# slimarm_apricot_nand.net
KiCad netlist of a schematic drawn in EasyEDA Pro
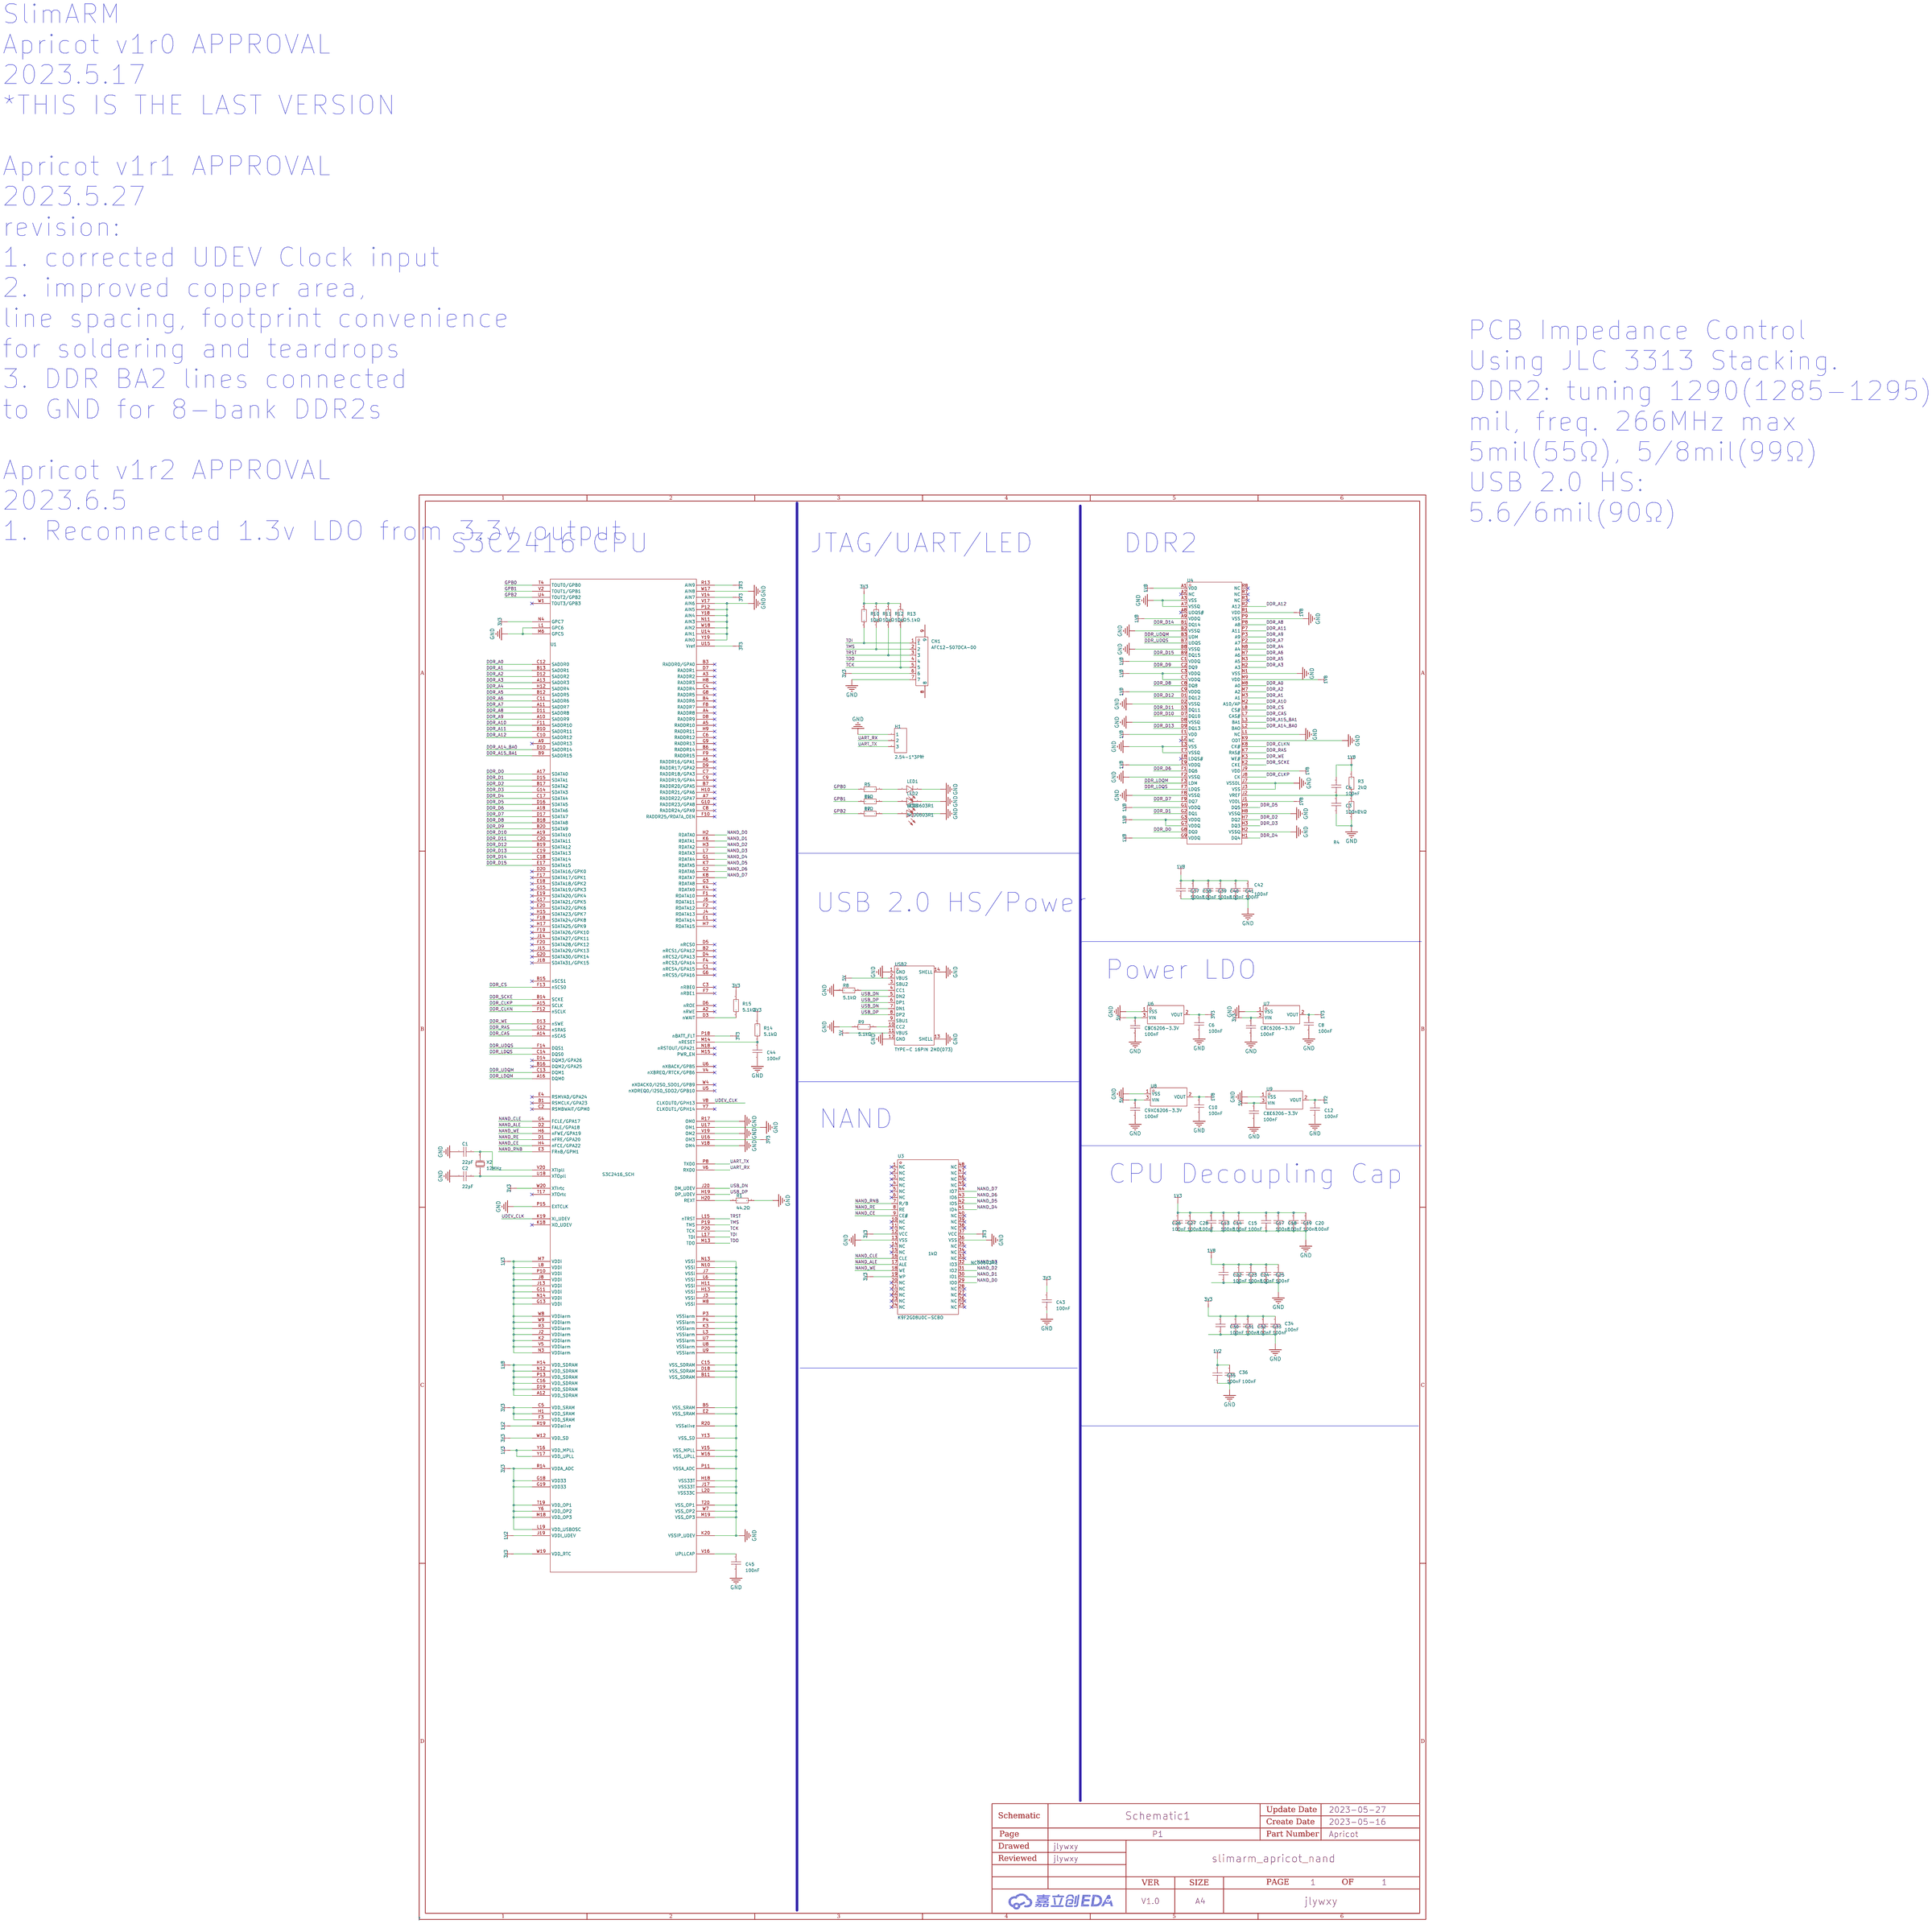
[diagram p0: schematic sheet]

(export (version "E")
  (design (tool "Eeschema 10.0.6"))
  (components
    (comp (ref "C1")
      (value "22pF")
      (footprint "easyedapro:C0402")
      (description "容值:22pF;精度:±5%;额定电压:50V;材质(温度系数):NP0;")
      (fields
        (field (name "Manufacturer Part") "CC0402JRNPO9BN220")
        (field (name "Manufacturer") "YAGEO(国巨)")
      )
      (libsource (lib "easyedapro") (part "CC0402JRNPO9BN220"))
    )
    (comp (ref "C2")
      (value "22pF")
      (footprint "easyedapro:C0402")
      (description "容值:22pF;精度:±5%;额定电压:50V;材质(温度系数):NP0;")
      (fields
        (field (name "Manufacturer Part") "CC0402JRNPO9BN220")
        (field (name "Manufacturer") "YAGEO(国巨)")
      )
      (libsource (lib "easyedapro") (part "CC0402JRNPO9BN220"))
    )
    (comp (ref "C3")
      (value "100nF")
      (footprint "easyedapro:C0402")
      (description "容值:22pF;精度:±5%;额定电压:50V;材质(温度系数):NP0;")
      (fields
        (field (name "Manufacturer Part") "CC0402JRNPO9BN220")
        (field (name "Manufacturer") "YAGEO(国巨)")
      )
      (libsource (lib "easyedapro") (part "CC0402JRNPO9BN220"))
    )
    (comp (ref "C4")
      (value "100nF")
      (footprint "easyedapro:C0402")
      (description "容值:22pF;精度:±5%;额定电压:50V;材质(温度系数):NP0;")
      (fields
        (field (name "Manufacturer Part") "CC0402JRNPO9BN220")
        (field (name "Manufacturer") "YAGEO(国巨)")
      )
      (libsource (lib "easyedapro") (part "CC0402JRNPO9BN220"))
    )
    (comp (ref "C5")
      (value "100nF")
      (footprint "easyedapro:C0402")
      (description "容值:22pF;精度:±5%;额定电压:50V;材质(温度系数):NP0;")
      (fields
        (field (name "Manufacturer Part") "CC0402JRNPO9BN220")
        (field (name "Manufacturer") "YAGEO(国巨)")
      )
      (libsource (lib "easyedapro") (part "CC0402JRNPO9BN220"))
    )
    (comp (ref "C6")
      (value "100nF")
      (footprint "easyedapro:C0402")
      (description "容值:22pF;精度:±5%;额定电压:50V;材质(温度系数):NP0;")
      (fields
        (field (name "Manufacturer Part") "CC0402JRNPO9BN220")
        (field (name "Manufacturer") "YAGEO(国巨)")
      )
      (libsource (lib "easyedapro") (part "CC0402JRNPO9BN220"))
    )
    (comp (ref "C7")
      (value "100nF")
      (footprint "easyedapro:C0402")
      (description "容值:22pF;精度:±5%;额定电压:50V;材质(温度系数):NP0;")
      (fields
        (field (name "Manufacturer Part") "CC0402JRNPO9BN220")
        (field (name "Manufacturer") "YAGEO(国巨)")
      )
      (libsource (lib "easyedapro") (part "CC0402JRNPO9BN220"))
    )
    (comp (ref "C8")
      (value "100nF")
      (footprint "easyedapro:C0402")
      (description "容值:22pF;精度:±5%;额定电压:50V;材质(温度系数):NP0;")
      (fields
        (field (name "Manufacturer Part") "CC0402JRNPO9BN220")
        (field (name "Manufacturer") "YAGEO(国巨)")
      )
      (libsource (lib "easyedapro") (part "CC0402JRNPO9BN220"))
    )
    (comp (ref "C9")
      (value "100nF")
      (footprint "easyedapro:C0402")
      (description "容值:22pF;精度:±5%;额定电压:50V;材质(温度系数):NP0;")
      (fields
        (field (name "Manufacturer Part") "CC0402JRNPO9BN220")
        (field (name "Manufacturer") "YAGEO(国巨)")
      )
      (libsource (lib "easyedapro") (part "CC0402JRNPO9BN220"))
    )
    (comp (ref "C10")
      (value "100nF")
      (footprint "easyedapro:C0402")
      (description "容值:22pF;精度:±5%;额定电压:50V;材质(温度系数):NP0;")
      (fields
        (field (name "Manufacturer Part") "CC0402JRNPO9BN220")
        (field (name "Manufacturer") "YAGEO(国巨)")
      )
      (libsource (lib "easyedapro") (part "CC0402JRNPO9BN220"))
    )
    (comp (ref "C11")
      (value "100nF")
      (footprint "easyedapro:C0402")
      (description "容值:22pF;精度:±5%;额定电压:50V;材质(温度系数):NP0;")
      (fields
        (field (name "Manufacturer Part") "CC0402JRNPO9BN220")
        (field (name "Manufacturer") "YAGEO(国巨)")
      )
      (libsource (lib "easyedapro") (part "CC0402JRNPO9BN220"))
    )
    (comp (ref "C12")
      (value "100nF")
      (footprint "easyedapro:C0402")
      (description "容值:22pF;精度:±5%;额定电压:50V;材质(温度系数):NP0;")
      (fields
        (field (name "Manufacturer Part") "CC0402JRNPO9BN220")
        (field (name "Manufacturer") "YAGEO(国巨)")
      )
      (libsource (lib "easyedapro") (part "CC0402JRNPO9BN220"))
    )
    (comp (ref "C13")
      (value "100nF")
      (footprint "easyedapro:C0402")
      (description "容值:22pF;精度:±5%;额定电压:50V;材质(温度系数):NP0;")
      (fields
        (field (name "Manufacturer Part") "CC0402JRNPO9BN220")
        (field (name "Manufacturer") "YAGEO(国巨)")
      )
      (libsource (lib "easyedapro") (part "CC0402JRNPO9BN220"))
    )
    (comp (ref "C14")
      (value "100nF")
      (footprint "easyedapro:C0402")
      (description "容值:22pF;精度:±5%;额定电压:50V;材质(温度系数):NP0;")
      (fields
        (field (name "Manufacturer Part") "CC0402JRNPO9BN220")
        (field (name "Manufacturer") "YAGEO(国巨)")
      )
      (libsource (lib "easyedapro") (part "CC0402JRNPO9BN220"))
    )
    (comp (ref "C15")
      (value "100nF")
      (footprint "easyedapro:C0402")
      (description "容值:22pF;精度:±5%;额定电压:50V;材质(温度系数):NP0;")
      (fields
        (field (name "Manufacturer Part") "CC0402JRNPO9BN220")
        (field (name "Manufacturer") "YAGEO(国巨)")
      )
      (libsource (lib "easyedapro") (part "CC0402JRNPO9BN220"))
    )
    (comp (ref "C17")
      (value "100nF")
      (footprint "easyedapro:C0402")
      (description "容值:22pF;精度:±5%;额定电压:50V;材质(温度系数):NP0;")
      (fields
        (field (name "Manufacturer Part") "CC0402JRNPO9BN220")
        (field (name "Manufacturer") "YAGEO(国巨)")
      )
      (libsource (lib "easyedapro") (part "CC0402JRNPO9BN220"))
    )
    (comp (ref "C18")
      (value "100nF")
      (footprint "easyedapro:C0402")
      (description "容值:22pF;精度:±5%;额定电压:50V;材质(温度系数):NP0;")
      (fields
        (field (name "Manufacturer Part") "CC0402JRNPO9BN220")
        (field (name "Manufacturer") "YAGEO(国巨)")
      )
      (libsource (lib "easyedapro") (part "CC0402JRNPO9BN220"))
    )
    (comp (ref "C19")
      (value "100nF")
      (footprint "easyedapro:C0402")
      (description "容值:22pF;精度:±5%;额定电压:50V;材质(温度系数):NP0;")
      (fields
        (field (name "Manufacturer Part") "CC0402JRNPO9BN220")
        (field (name "Manufacturer") "YAGEO(国巨)")
      )
      (libsource (lib "easyedapro") (part "CC0402JRNPO9BN220"))
    )
    (comp (ref "C20")
      (value "100nF")
      (footprint "easyedapro:C0402")
      (description "容值:22pF;精度:±5%;额定电压:50V;材质(温度系数):NP0;")
      (fields
        (field (name "Manufacturer Part") "CC0402JRNPO9BN220")
        (field (name "Manufacturer") "YAGEO(国巨)")
      )
      (libsource (lib "easyedapro") (part "CC0402JRNPO9BN220"))
    )
    (comp (ref "C22")
      (value "100nF")
      (footprint "easyedapro:C0402")
      (description "容值:22pF;精度:±5%;额定电压:50V;材质(温度系数):NP0;")
      (fields
        (field (name "Manufacturer Part") "CC0402JRNPO9BN220")
        (field (name "Manufacturer") "YAGEO(国巨)")
      )
      (libsource (lib "easyedapro") (part "CC0402JRNPO9BN220"))
    )
    (comp (ref "C23")
      (value "100nF")
      (footprint "easyedapro:C0402")
      (description "容值:22pF;精度:±5%;额定电压:50V;材质(温度系数):NP0;")
      (fields
        (field (name "Manufacturer Part") "CC0402JRNPO9BN220")
        (field (name "Manufacturer") "YAGEO(国巨)")
      )
      (libsource (lib "easyedapro") (part "CC0402JRNPO9BN220"))
    )
    (comp (ref "C24")
      (value "100nF")
      (footprint "easyedapro:C0402")
      (description "容值:22pF;精度:±5%;额定电压:50V;材质(温度系数):NP0;")
      (fields
        (field (name "Manufacturer Part") "CC0402JRNPO9BN220")
        (field (name "Manufacturer") "YAGEO(国巨)")
      )
      (libsource (lib "easyedapro") (part "CC0402JRNPO9BN220"))
    )
    (comp (ref "C25")
      (value "100nF")
      (footprint "easyedapro:C0402")
      (description "容值:22pF;精度:±5%;额定电压:50V;材质(温度系数):NP0;")
      (fields
        (field (name "Manufacturer Part") "CC0402JRNPO9BN220")
        (field (name "Manufacturer") "YAGEO(国巨)")
      )
      (libsource (lib "easyedapro") (part "CC0402JRNPO9BN220"))
    )
    (comp (ref "C26")
      (value "100nF")
      (footprint "easyedapro:C0402")
      (description "容值:22pF;精度:±5%;额定电压:50V;材质(温度系数):NP0;")
      (fields
        (field (name "Manufacturer Part") "CC0402JRNPO9BN220")
        (field (name "Manufacturer") "YAGEO(国巨)")
      )
      (libsource (lib "easyedapro") (part "CC0402JRNPO9BN220"))
    )
    (comp (ref "C27")
      (value "100nF")
      (footprint "easyedapro:C0402")
      (description "容值:22pF;精度:±5%;额定电压:50V;材质(温度系数):NP0;")
      (fields
        (field (name "Manufacturer Part") "CC0402JRNPO9BN220")
        (field (name "Manufacturer") "YAGEO(国巨)")
      )
      (libsource (lib "easyedapro") (part "CC0402JRNPO9BN220"))
    )
    (comp (ref "C28")
      (value "100nF")
      (footprint "easyedapro:C0402")
      (description "容值:22pF;精度:±5%;额定电压:50V;材质(温度系数):NP0;")
      (fields
        (field (name "Manufacturer Part") "CC0402JRNPO9BN220")
        (field (name "Manufacturer") "YAGEO(国巨)")
      )
      (libsource (lib "easyedapro") (part "CC0402JRNPO9BN220"))
    )
    (comp (ref "C30")
      (value "100nF")
      (footprint "easyedapro:C0402")
      (description "容值:22pF;精度:±5%;额定电压:50V;材质(温度系数):NP0;")
      (fields
        (field (name "Manufacturer Part") "CC0402JRNPO9BN220")
        (field (name "Manufacturer") "YAGEO(国巨)")
      )
      (libsource (lib "easyedapro") (part "CC0402JRNPO9BN220"))
    )
    (comp (ref "C31")
      (value "100nF")
      (footprint "easyedapro:C0402")
      (description "容值:22pF;精度:±5%;额定电压:50V;材质(温度系数):NP0;")
      (fields
        (field (name "Manufacturer Part") "CC0402JRNPO9BN220")
        (field (name "Manufacturer") "YAGEO(国巨)")
      )
      (libsource (lib "easyedapro") (part "CC0402JRNPO9BN220"))
    )
    (comp (ref "C32")
      (value "100nF")
      (footprint "easyedapro:C0402")
      (description "容值:22pF;精度:±5%;额定电压:50V;材质(温度系数):NP0;")
      (fields
        (field (name "Manufacturer Part") "CC0402JRNPO9BN220")
        (field (name "Manufacturer") "YAGEO(国巨)")
      )
      (libsource (lib "easyedapro") (part "CC0402JRNPO9BN220"))
    )
    (comp (ref "C33")
      (value "100nF")
      (footprint "easyedapro:C0402")
      (description "容值:22pF;精度:±5%;额定电压:50V;材质(温度系数):NP0;")
      (fields
        (field (name "Manufacturer Part") "CC0402JRNPO9BN220")
        (field (name "Manufacturer") "YAGEO(国巨)")
      )
      (libsource (lib "easyedapro") (part "CC0402JRNPO9BN220"))
    )
    (comp (ref "C34")
      (value "100nF")
      (footprint "easyedapro:C0402")
      (description "容值:22pF;精度:±5%;额定电压:50V;材质(温度系数):NP0;")
      (fields
        (field (name "Manufacturer Part") "CC0402JRNPO9BN220")
        (field (name "Manufacturer") "YAGEO(国巨)")
      )
      (libsource (lib "easyedapro") (part "CC0402JRNPO9BN220"))
    )
    (comp (ref "C35")
      (value "100nF")
      (footprint "easyedapro:C0402")
      (description "容值:22pF;精度:±5%;额定电压:50V;材质(温度系数):NP0;")
      (fields
        (field (name "Manufacturer Part") "CC0402JRNPO9BN220")
        (field (name "Manufacturer") "YAGEO(国巨)")
      )
      (libsource (lib "easyedapro") (part "CC0402JRNPO9BN220"))
    )
    (comp (ref "C36")
      (value "100nF")
      (footprint "easyedapro:C0402")
      (description "容值:22pF;精度:±5%;额定电压:50V;材质(温度系数):NP0;")
      (fields
        (field (name "Manufacturer Part") "CC0402JRNPO9BN220")
        (field (name "Manufacturer") "YAGEO(国巨)")
      )
      (libsource (lib "easyedapro") (part "CC0402JRNPO9BN220"))
    )
    (comp (ref "C37")
      (value "100nF")
      (footprint "easyedapro:C0402")
      (description "容值:22pF;精度:±5%;额定电压:50V;材质(温度系数):NP0;")
      (fields
        (field (name "Manufacturer Part") "CC0402JRNPO9BN220")
        (field (name "Manufacturer") "YAGEO(国巨)")
      )
      (libsource (lib "easyedapro") (part "CC0402JRNPO9BN220"))
    )
    (comp (ref "C38")
      (value "100nF")
      (footprint "easyedapro:C0402")
      (description "容值:22pF;精度:±5%;额定电压:50V;材质(温度系数):NP0;")
      (fields
        (field (name "Manufacturer Part") "CC0402JRNPO9BN220")
        (field (name "Manufacturer") "YAGEO(国巨)")
      )
      (libsource (lib "easyedapro") (part "CC0402JRNPO9BN220"))
    )
    (comp (ref "C39")
      (value "100nF")
      (footprint "easyedapro:C0402")
      (description "容值:22pF;精度:±5%;额定电压:50V;材质(温度系数):NP0;")
      (fields
        (field (name "Manufacturer Part") "CC0402JRNPO9BN220")
        (field (name "Manufacturer") "YAGEO(国巨)")
      )
      (libsource (lib "easyedapro") (part "CC0402JRNPO9BN220"))
    )
    (comp (ref "C40")
      (value "100nF")
      (footprint "easyedapro:C0402")
      (description "容值:22pF;精度:±5%;额定电压:50V;材质(温度系数):NP0;")
      (fields
        (field (name "Manufacturer Part") "CC0402JRNPO9BN220")
        (field (name "Manufacturer") "YAGEO(国巨)")
      )
      (libsource (lib "easyedapro") (part "CC0402JRNPO9BN220"))
    )
    (comp (ref "C41")
      (value "100nF")
      (footprint "easyedapro:C0402")
      (description "容值:22pF;精度:±5%;额定电压:50V;材质(温度系数):NP0;")
      (fields
        (field (name "Manufacturer Part") "CC0402JRNPO9BN220")
        (field (name "Manufacturer") "YAGEO(国巨)")
      )
      (libsource (lib "easyedapro") (part "CC0402JRNPO9BN220"))
    )
    (comp (ref "C42")
      (value "100nF")
      (footprint "easyedapro:C0402")
      (description "容值:22pF;精度:±5%;额定电压:50V;材质(温度系数):NP0;")
      (fields
        (field (name "Manufacturer Part") "CC0402JRNPO9BN220")
        (field (name "Manufacturer") "YAGEO(国巨)")
      )
      (libsource (lib "easyedapro") (part "CC0402JRNPO9BN220"))
    )
    (comp (ref "C43")
      (value "100nF")
      (footprint "easyedapro:C0402")
      (description "容值:22pF;精度:±5%;额定电压:50V;材质(温度系数):NP0;")
      (fields
        (field (name "Manufacturer Part") "CC0402JRNPO9BN220")
        (field (name "Manufacturer") "YAGEO(国巨)")
      )
      (libsource (lib "easyedapro") (part "CC0402JRNPO9BN220"))
    )
    (comp (ref "C44")
      (value "100nF")
      (footprint "easyedapro:C0402")
      (description "容值:22pF;精度:±5%;额定电压:50V;材质(温度系数):NP0;")
      (fields
        (field (name "Manufacturer Part") "CC0402JRNPO9BN220")
        (field (name "Manufacturer") "YAGEO(国巨)")
      )
      (libsource (lib "easyedapro") (part "CC0402JRNPO9BN220"))
    )
    (comp (ref "C45")
      (value "100nF")
      (footprint "easyedapro:C0402")
      (description "容值:22pF;精度:±5%;额定电压:50V;材质(温度系数):NP0;")
      (fields
        (field (name "Manufacturer Part") "CC0402JRNPO9BN220")
        (field (name "Manufacturer") "YAGEO(国巨)")
      )
      (libsource (lib "easyedapro") (part "CC0402JRNPO9BN220"))
    )
    (comp (ref "CN1")
      (value "AFC12-S07DCA-00")
      (footprint "easyedapro:CONN-SMD_AFC12-S07DCA-00")
      (description "参考系列:-;间距:1.25mm;插针结构:1x7P;排数:1;每排PIN数:7;行距:-;公母:公型插针;安装方式:卧贴;额定电流:1A;工作温度范围:-20°C~+85°C;")
      (fields (field (name "Manufacturer") "JS(钜硕电子)"))
      (libsource (lib "easyedapro") (part "AFC12-S07DCA-00"))
    )
    (comp (ref "H1")
      (value "2.54-1*3P针")
      (footprint "easyedapro:HDR-TH_3P-P2.54-V-M-1")
      (fields (field (name "Manufacturer") "BOOMELE(博穆精密)"))
      (libsource (lib "easyedapro") (part "Header-Male-2.54_1x3"))
    )
    (comp (ref "LED1")
      (value "NCD0603R1")
      (footprint "easyedapro:LED0603-RD_RED")
      (description "发光颜色:红灯;")
      (fields (field (name "Manufacturer") "国星光电"))
      (libsource (lib "easyedapro") (part "FC-DA1608HRK-620D"))
    )
    (comp (ref "LED2")
      (value "NCD0603R1")
      (footprint "easyedapro:LED0603-RD_RED")
      (description "发光颜色:红灯;")
      (fields (field (name "Manufacturer") "国星光电"))
      (libsource (lib "easyedapro") (part "FC-DA1608HRK-620D"))
    )
    (comp (ref "LED3")
      (value "NCD0603R1")
      (footprint "easyedapro:LED0603-RD_RED")
      (description "发光颜色:红灯;")
      (fields (field (name "Manufacturer") "国星光电"))
      (libsource (lib "easyedapro") (part "FC-DA1608HRK-620D"))
    )
    (comp (ref "R1")
      (value "44.2Ω")
      (footprint "easyedapro:R0402")
      (description "阻值:44.2Ω;精度:±1%;功率:62.5mW;")
      (fields (field (name "Manufacturer Part") "RCT0244R2FLF") (field (name "Manufacturer") "HKR"))
      (libsource (lib "easyedapro") (part "RCT0244R2FLF"))
    )
    (comp (ref "R3")
      (value "2kΩ")
      (footprint "easyedapro:R0402")
      (description "阻值:44.2Ω;精度:±1%;功率:62.5mW;")
      (fields (field (name "Manufacturer Part") "RCT0244R2FLF") (field (name "Manufacturer") "HKR"))
      (libsource (lib "easyedapro") (part "RCT0244R2FLF"))
    )
    (comp (ref "R4")
      (value "2kΩ")
      (footprint "easyedapro:R0402")
      (description "阻值:44.2Ω;精度:±1%;功率:62.5mW;")
      (fields (field (name "Manufacturer Part") "RCT0244R2FLF") (field (name "Manufacturer") "HKR"))
      (libsource (lib "easyedapro") (part "RCT0244R2FLF"))
    )
    (comp (ref "R5")
      (value "1kΩ")
      (footprint "easyedapro:R0603")
      (description "电阻类型:厚膜电阻;阻值:1kΩ;精度:±1%;功率:100mW;")
      (fields
        (field (name "Manufacturer Part") "0603WAF1001T5E")
        (field (name "Manufacturer") "UNI-ROYAL(厚声)")
      )
      (libsource (lib "easyedapro") (part "0603WAF1001T5E"))
    )
    (comp (ref "R6")
      (value "1kΩ")
      (footprint "easyedapro:R0603")
      (description "电阻类型:厚膜电阻;阻值:1kΩ;精度:±1%;功率:100mW;")
      (fields
        (field (name "Manufacturer Part") "0603WAF1001T5E")
        (field (name "Manufacturer") "UNI-ROYAL(厚声)")
      )
      (libsource (lib "easyedapro") (part "0603WAF1001T5E"))
    )
    (comp (ref "R7")
      (value "1kΩ")
      (footprint "easyedapro:R0603")
      (description "电阻类型:厚膜电阻;阻值:1kΩ;精度:±1%;功率:100mW;")
      (fields
        (field (name "Manufacturer Part") "0603WAF1001T5E")
        (field (name "Manufacturer") "UNI-ROYAL(厚声)")
      )
      (libsource (lib "easyedapro") (part "0603WAF1001T5E"))
    )
    (comp (ref "R8")
      (value "5.1kΩ")
      (footprint "easyedapro:R0402")
      (description "电阻类型:厚膜电阻;阻值:5.1kΩ;精度:±1%;功率:62.5mW;")
      (fields
        (field (name "Manufacturer Part") "0402WGF5101TCE")
        (field (name "Manufacturer") "UNI-ROYAL(厚声)")
      )
      (libsource (lib "easyedapro") (part "0402WGF5101TCE"))
    )
    (comp (ref "R9")
      (value "5.1kΩ")
      (footprint "easyedapro:R0402")
      (description "电阻类型:厚膜电阻;阻值:5.1kΩ;精度:±1%;功率:62.5mW;")
      (fields
        (field (name "Manufacturer Part") "0402WGF5101TCE")
        (field (name "Manufacturer") "UNI-ROYAL(厚声)")
      )
      (libsource (lib "easyedapro") (part "0402WGF5101TCE"))
    )
    (comp (ref "R10")
      (value "10kΩ")
      (footprint "easyedapro:R0402")
      (description "电阻类型:厚膜电阻;阻值:5.1kΩ;精度:±1%;功率:62.5mW;")
      (fields
        (field (name "Manufacturer Part") "0402WGF5101TCE")
        (field (name "Manufacturer") "UNI-ROYAL(厚声)")
      )
      (libsource (lib "easyedapro") (part "0402WGF5101TCE"))
    )
    (comp (ref "R11")
      (value "10kΩ")
      (footprint "easyedapro:R0402")
      (description "电阻类型:厚膜电阻;阻值:5.1kΩ;精度:±1%;功率:62.5mW;")
      (fields
        (field (name "Manufacturer Part") "0402WGF5101TCE")
        (field (name "Manufacturer") "UNI-ROYAL(厚声)")
      )
      (libsource (lib "easyedapro") (part "0402WGF5101TCE"))
    )
    (comp (ref "R12")
      (value "10kΩ")
      (footprint "easyedapro:R0402")
      (description "电阻类型:厚膜电阻;阻值:5.1kΩ;精度:±1%;功率:62.5mW;")
      (fields
        (field (name "Manufacturer Part") "0402WGF5101TCE")
        (field (name "Manufacturer") "UNI-ROYAL(厚声)")
      )
      (libsource (lib "easyedapro") (part "0402WGF5101TCE"))
    )
    (comp (ref "R13")
      (value "5.1kΩ")
      (footprint "easyedapro:R0402")
      (description "电阻类型:厚膜电阻;阻值:5.1kΩ;精度:±1%;功率:62.5mW;")
      (fields
        (field (name "Manufacturer Part") "0402WGF5101TCE")
        (field (name "Manufacturer") "UNI-ROYAL(厚声)")
      )
      (libsource (lib "easyedapro") (part "0402WGF5101TCE"))
    )
    (comp (ref "R14")
      (value "5.1kΩ")
      (footprint "easyedapro:R0402")
      (description "电阻类型:厚膜电阻;阻值:5.1kΩ;精度:±1%;功率:62.5mW;")
      (fields
        (field (name "Manufacturer Part") "0402WGF5101TCE")
        (field (name "Manufacturer") "UNI-ROYAL(厚声)")
      )
      (libsource (lib "easyedapro") (part "0402WGF5101TCE"))
    )
    (comp (ref "R15")
      (value "5.1kΩ")
      (footprint "easyedapro:R0402")
      (description "电阻类型:厚膜电阻;阻值:5.1kΩ;精度:±1%;功率:62.5mW;")
      (fields
        (field (name "Manufacturer Part") "0402WGF5101TCE")
        (field (name "Manufacturer") "UNI-ROYAL(厚声)")
      )
      (libsource (lib "easyedapro") (part "0402WGF5101TCE"))
    )
    (comp (ref "U1") (value "S3C2416_SCH") (libsource (lib "easyedapro") (part "S3C2416_SCH")))
    (comp (ref "U3")
      (value "K9F2G08U0C-SCBO")
      (footprint "easyedapro:TSOP-48_L12.0-W18.4-P0.50-LS20.0-BL")
      (description "存储器构架(格式):FLASH;存储器接口类型:Parallel;存储器容量:2Gb (256M x 8);存储器类型:Non-Volatile;")
      (libsource (lib "easyedapro") (part "K9F2G08UOC-SCBO"))
    )
    (comp (ref "U4")
      (value "NT5TU32M16FG-AC")
      (footprint "easyedapro:VFBGA-84_L7.5-W12.2-P0.80-TL_NANYA_NT5TU32M16FG")
      (fields (field (name "Manufacturer") "Nanya(南亚科技)"))
      (libsource (lib "easyedapro") (part "NT5TU32M16FG-AC"))
    )
    (comp (ref "U6")
      (value "XC6206-3.3V")
      (footprint "easyedapro:SSOT-3_L2.9-W1.6-P0.95-LS2.8-BR")
      (description "输出类型:固定;输出极性:正;最大输入电压:6V;输出电压:3.3V;输出电流:250mA;")
      (fields (field (name "Manufacturer") "YONGYUTAI(永裕泰)"))
      (libsource (lib "easyedapro") (part "XC6206-3.3V"))
    )
    (comp (ref "U7")
      (value "XC6206-3.3V")
      (footprint "easyedapro:SSOT-3_L2.9-W1.6-P0.95-LS2.8-BR")
      (description "输出类型:固定;输出极性:正;最大输入电压:6V;输出电压:3.3V;输出电流:250mA;")
      (fields (field (name "Manufacturer") "YONGYUTAI(永裕泰)"))
      (libsource (lib "easyedapro") (part "XC6206-3.3V"))
    )
    (comp (ref "U8")
      (value "XC6206-3.3V")
      (footprint "easyedapro:SSOT-3_L2.9-W1.6-P0.95-LS2.8-BR")
      (description "输出类型:固定;输出极性:正;最大输入电压:6V;输出电压:3.3V;输出电流:250mA;")
      (fields (field (name "Manufacturer") "YONGYUTAI(永裕泰)"))
      (libsource (lib "easyedapro") (part "XC6206-3.3V"))
    )
    (comp (ref "U9")
      (value "XC6206-3.3V")
      (footprint "easyedapro:SSOT-3_L2.9-W1.6-P0.95-LS2.8-BR")
      (description "输出类型:固定;输出极性:正;最大输入电压:6V;输出电压:3.3V;输出电流:250mA;")
      (fields (field (name "Manufacturer") "YONGYUTAI(永裕泰)"))
      (libsource (lib "easyedapro") (part "XC6206-3.3V"))
    )
    (comp (ref "USB2")
      (value "TYPE-C 16PIN 2MD(073)")
      (footprint "easyedapro:USB-C-SMD_TYPE-C-6PIN-2MD-073")
      (description "连接器类型:Type-C;标准:-;公母:母座;触点数量:16;端口数量:1;安装方式:卧贴;额定电流 - 电源:5A;工作温度范围:-25°C~+85°C;")
      (fields (field (name "Manufacturer") "SHOU HAN(首韩)"))
      (libsource (lib "easyedapro") (part "TYPE-C 16PIN 2MD(073)"))
    )
    (comp (ref "X2")
      (value "12MHz")
      (footprint "easyedapro:CRYSTAL-SMD_L5.0-W3.2")
      (description "频率:8MHz;频率公差:±10ppm;负载电容:20pF;")
      (fields (field (name "Manufacturer Part") "X50328MSB2GI") (field (name "Manufacturer") "YXC(扬兴晶振)"))
      (libsource (lib "easyedapro") (part "X50328MSB2GI"))
    )
  )
  (nets
    (net (code "1") (name "/DDR_A0") (class "Default")
      (node (ref "U1") (pin "C12") (pinfunction "SADDR0_C12") (pintype "input"))
      (node (ref "U4") (pin "M8") (pinfunction "A0_M8") (pintype "input"))
    )
    (net (code "2") (name "/DDR_A1") (class "Default")
      (node (ref "U1") (pin "B13") (pinfunction "SADDR1_B13") (pintype "input"))
      (node (ref "U4") (pin "M3") (pinfunction "A1_M3") (pintype "input"))
    )
    (net (code "3") (name "/DDR_A2") (class "Default")
      (node (ref "U1") (pin "D12") (pinfunction "SADDR2_D12") (pintype "input"))
      (node (ref "U4") (pin "M7") (pinfunction "A2_M7") (pintype "input"))
    )
    (net (code "4") (name "/DDR_A3") (class "Default")
      (node (ref "U1") (pin "A13") (pinfunction "SADDR3_A13") (pintype "input"))
      (node (ref "U4") (pin "N2") (pinfunction "A3_N2") (pintype "input"))
    )
    (net (code "5") (name "/DDR_A4") (class "Default")
      (node (ref "U1") (pin "H12") (pinfunction "SADDR4_H12") (pintype "input"))
      (node (ref "U4") (pin "N8") (pinfunction "A4_N8") (pintype "input"))
    )
    (net (code "6") (name "/DDR_A5") (class "Default")
      (node (ref "U1") (pin "B12") (pinfunction "SADDR5_B12") (pintype "input"))
      (node (ref "U4") (pin "N3") (pinfunction "A5_N3") (pintype "input"))
    )
    (net (code "7") (name "/DDR_A6") (class "Default")
      (node (ref "U1") (pin "C11") (pinfunction "SADDR6_C11") (pintype "input"))
      (node (ref "U4") (pin "N7") (pinfunction "A6_N7") (pintype "input"))
    )
    (net (code "8") (name "/DDR_A7") (class "Default")
      (node (ref "U1") (pin "A11") (pinfunction "SADDR7_A11") (pintype "input"))
      (node (ref "U4") (pin "P2") (pinfunction "A7_P2") (pintype "input"))
    )
    (net (code "9") (name "/DDR_A8") (class "Default")
      (node (ref "U1") (pin "D11") (pinfunction "SADDR8_D11") (pintype "input"))
      (node (ref "U4") (pin "P8") (pinfunction "A8_P8") (pintype "input"))
    )
    (net (code "10") (name "/DDR_A9") (class "Default")
      (node (ref "U1") (pin "A10") (pinfunction "SADDR9_A10") (pintype "input"))
      (node (ref "U4") (pin "P3") (pinfunction "A9_P3") (pintype "input"))
    )
    (net (code "11") (name "/DDR_A10") (class "Default")
      (node (ref "U1") (pin "F11") (pinfunction "SADDR10_F11") (pintype "input"))
      (node (ref "U4") (pin "M2") (pinfunction "A10/AP_M2") (pintype "input"))
    )
    (net (code "12") (name "/DDR_A11") (class "Default")
      (node (ref "U1") (pin "B10") (pinfunction "SADDR11_B10") (pintype "input"))
      (node (ref "U4") (pin "P7") (pinfunction "A11_P7") (pintype "input"))
    )
    (net (code "13") (name "/DDR_A12") (class "Default")
      (node (ref "U1") (pin "C10") (pinfunction "SADDR12_C10") (pintype "input"))
      (node (ref "U4") (pin "R2") (pinfunction "A12_R2") (pintype "input"))
    )
    (net (code "14") (name "/DDR_A14_BA0") (class "Default")
      (node (ref "U1") (pin "D10") (pinfunction "SADDR14_D10") (pintype "input"))
      (node (ref "U4") (pin "L2") (pinfunction "BAO_L2") (pintype "input"))
    )
    (net (code "15") (name "/DDR_A15_BA1") (class "Default")
      (node (ref "U1") (pin "B9") (pinfunction "SADDR15_B9") (pintype "input"))
      (node (ref "U4") (pin "L3") (pinfunction "BA1_L3") (pintype "input"))
    )
    (net (code "16") (name "/DDR_CAS") (class "Default")
      (node (ref "U1") (pin "A14") (pinfunction "nSCAS_A14") (pintype "input"))
      (node (ref "U4") (pin "L7") (pinfunction "CAS#_L7") (pintype "input"))
    )
    (net (code "17") (name "/DDR_CLKN") (class "Default")
      (node (ref "U1") (pin "F12") (pinfunction "nSCLK_F12") (pintype "input"))
      (node (ref "U4") (pin "K8") (pinfunction "CK#_K8") (pintype "input"))
    )
    (net (code "18") (name "/DDR_CLKP") (class "Default")
      (node (ref "U1") (pin "A15") (pinfunction "SCLK_A15") (pintype "input"))
      (node (ref "U4") (pin "J8") (pinfunction "CK_J8") (pintype "input"))
    )
    (net (code "19") (name "/DDR_CS") (class "Default")
      (node (ref "U1") (pin "F13") (pinfunction "nSCS0_F13") (pintype "input"))
      (node (ref "U4") (pin "L8") (pinfunction "CS#_L8") (pintype "input"))
    )
    (net (code "20") (name "/DDR_D0") (class "Default")
      (node (ref "U1") (pin "A17") (pinfunction "SDATA0_A17") (pintype "input"))
      (node (ref "U4") (pin "G8") (pinfunction "DQ0_G8") (pintype "input"))
    )
    (net (code "21") (name "/DDR_D1") (class "Default")
      (node (ref "U1") (pin "D15") (pinfunction "SDATA1_D15") (pintype "input"))
      (node (ref "U4") (pin "G2") (pinfunction "DQ1_G2") (pintype "input"))
    )
    (net (code "22") (name "/DDR_D2") (class "Default")
      (node (ref "U1") (pin "B17") (pinfunction "SDATA2_B17") (pintype "input"))
      (node (ref "U4") (pin "H7") (pinfunction "DQ2_H7") (pintype "input"))
    )
    (net (code "23") (name "/DDR_D3") (class "Default")
      (node (ref "U1") (pin "G14") (pinfunction "SDATA3_G14") (pintype "input"))
      (node (ref "U4") (pin "H3") (pinfunction "DQ3_H3") (pintype "input"))
    )
    (net (code "24") (name "/DDR_D4") (class "Default")
      (node (ref "U1") (pin "C17") (pinfunction "SDATA4_C17") (pintype "input"))
      (node (ref "U4") (pin "H1") (pinfunction "DQ4_H1") (pintype "input"))
    )
    (net (code "25") (name "/DDR_D5") (class "Default")
      (node (ref "U1") (pin "D16") (pinfunction "SDATA5_D16") (pintype "input"))
      (node (ref "U4") (pin "H9") (pinfunction "DQ5_H9") (pintype "input"))
    )
    (net (code "26") (name "/DDR_D6") (class "Default")
      (node (ref "U1") (pin "A18") (pinfunction "SDATA6_A18") (pintype "input"))
      (node (ref "U4") (pin "F1") (pinfunction "DQ6_F1") (pintype "input"))
    )
    (net (code "27") (name "/DDR_D7") (class "Default")
      (node (ref "U1") (pin "D17") (pinfunction "SDATA7_D17") (pintype "input"))
      (node (ref "U4") (pin "F9") (pinfunction "DQ7_F9") (pintype "input"))
    )
    (net (code "28") (name "/DDR_D8") (class "Default")
      (node (ref "U1") (pin "B18") (pinfunction "SDATA8_B18") (pintype "input"))
      (node (ref "U4") (pin "C8") (pinfunction "DQ8_C8") (pintype "input"))
    )
    (net (code "29") (name "/DDR_D9") (class "Default")
      (node (ref "U1") (pin "B20") (pinfunction "SDATA9_B20") (pintype "input"))
      (node (ref "U4") (pin "C2") (pinfunction "DQ9_C2") (pintype "input"))
    )
    (net (code "30") (name "/DDR_D10") (class "Default")
      (node (ref "U1") (pin "A19") (pinfunction "SDATA10_A19") (pintype "input"))
      (node (ref "U4") (pin "D7") (pinfunction "DQ10_D7") (pintype "input"))
    )
    (net (code "31") (name "/DDR_D11") (class "Default")
      (node (ref "U1") (pin "C20") (pinfunction "SDATA11_C20") (pintype "input"))
      (node (ref "U4") (pin "D3") (pinfunction "DQ11_D3") (pintype "input"))
    )
    (net (code "32") (name "/DDR_D12") (class "Default")
      (node (ref "U1") (pin "B19") (pinfunction "SDATA12_B19") (pintype "input"))
      (node (ref "U4") (pin "D1") (pinfunction "DQ12_D1") (pintype "input"))
    )
    (net (code "33") (name "/DDR_D13") (class "Default")
      (node (ref "U1") (pin "C19") (pinfunction "SDATA13_C19") (pintype "input"))
      (node (ref "U4") (pin "D9") (pinfunction "DQ13_D9") (pintype "input"))
    )
    (net (code "34") (name "/DDR_D14") (class "Default")
      (node (ref "U1") (pin "C18") (pinfunction "SDATA14_C18") (pintype "input"))
      (node (ref "U4") (pin "B1") (pinfunction "DQ14_B1") (pintype "input"))
    )
    (net (code "35") (name "/DDR_D15") (class "Default")
      (node (ref "U1") (pin "E17") (pinfunction "SDATA15_E17") (pintype "input"))
      (node (ref "U4") (pin "B9") (pinfunction "DQ15_B9") (pintype "input"))
    )
    (net (code "36") (name "/DDR_LDQM") (class "Default")
      (node (ref "U1") (pin "A16") (pinfunction "DQM0_A16") (pintype "input"))
      (node (ref "U4") (pin "F3") (pinfunction "LDM_F3") (pintype "input"))
    )
    (net (code "37") (name "/DDR_LDQS") (class "Default")
      (node (ref "U1") (pin "C14") (pinfunction "DQS0_C14") (pintype "input"))
      (node (ref "U4") (pin "F7") (pinfunction "LDQS_F7") (pintype "input"))
    )
    (net (code "38") (name "/DDR_RAS") (class "Default")
      (node (ref "U1") (pin "G12") (pinfunction "nSRAS_G12") (pintype "input"))
      (node (ref "U4") (pin "K7") (pinfunction "RAS#_K7") (pintype "input"))
    )
    (net (code "39") (name "/DDR_SCKE") (class "Default")
      (node (ref "U1") (pin "B14") (pinfunction "SCKE_B14") (pintype "input"))
      (node (ref "U4") (pin "K2") (pinfunction "CKE_K2") (pintype "input"))
    )
    (net (code "40") (name "/DDR_UDQM") (class "Default")
      (node (ref "U1") (pin "C13") (pinfunction "DQM1_C13") (pintype "input"))
      (node (ref "U4") (pin "B3") (pinfunction "UDM_B3") (pintype "input"))
    )
    (net (code "41") (name "/DDR_UDQS") (class "Default")
      (node (ref "U1") (pin "F14") (pinfunction "DQS1_F14") (pintype "input"))
      (node (ref "U4") (pin "B7") (pinfunction "UDQS_B7") (pintype "input"))
    )
    (net (code "42") (name "/DDR_WE") (class "Default")
      (node (ref "U1") (pin "D13") (pinfunction "nSWE_D13") (pintype "input"))
      (node (ref "U4") (pin "K3") (pinfunction "WE#_K3") (pintype "input"))
    )
    (net (code "43") (name "/GPB0") (class "Default")
      (node (ref "R5") (pin "1") (pinfunction "1_1") (pintype "input"))
      (node (ref "U1") (pin "T4") (pinfunction "TOUT0/GPB0_T4") (pintype "input"))
    )
    (net (code "44") (name "/GPB1") (class "Default")
      (node (ref "R6") (pin "1") (pinfunction "1_1") (pintype "input"))
      (node (ref "U1") (pin "V2") (pinfunction "TOUT1/GPB1_V2") (pintype "input"))
    )
    (net (code "45") (name "/GPB2") (class "Default")
      (node (ref "R7") (pin "1") (pinfunction "1_1") (pintype "input"))
      (node (ref "U1") (pin "U4") (pinfunction "TOUT2/GPB2_U4") (pintype "input"))
    )
    (net (code "46") (name "/NAND_ALE") (class "Default")
      (node (ref "U1") (pin "D2") (pinfunction "FALE/GPA18_D2") (pintype "input"))
      (node (ref "U3") (pin "17") (pinfunction "ALE_17") (pintype "input"))
    )
    (net (code "47") (name "/NAND_CE") (class "Default")
      (node (ref "U1") (pin "H4") (pinfunction "nFCE/GPA22_H4") (pintype "input"))
      (node (ref "U3") (pin "9") (pinfunction "CE#_9") (pintype "input"))
    )
    (net (code "48") (name "/NAND_CLE") (class "Default")
      (node (ref "U1") (pin "G4") (pinfunction "FCLE/GPA17_G4") (pintype "input"))
      (node (ref "U3") (pin "16") (pinfunction "CLE_16") (pintype "input"))
    )
    (net (code "49") (name "/NAND_D0") (class "Default")
      (node (ref "U1") (pin "H2") (pinfunction "RDATA0_H2") (pintype "input"))
      (node (ref "U3") (pin "29") (pinfunction "IO0_29") (pintype "input"))
    )
    (net (code "50") (name "/NAND_D1") (class "Default")
      (node (ref "U1") (pin "K6") (pinfunction "RDATA1_K6") (pintype "input"))
      (node (ref "U3") (pin "30") (pinfunction "IO1_30") (pintype "input"))
    )
    (net (code "51") (name "/NAND_D2") (class "Default")
      (node (ref "U1") (pin "H3") (pinfunction "RDATA2_H3") (pintype "input"))
      (node (ref "U3") (pin "31") (pinfunction "IO2_31") (pintype "input"))
    )
    (net (code "52") (name "/NAND_D3") (class "Default")
      (node (ref "U1") (pin "L7") (pinfunction "RDATA3_L7") (pintype "input"))
      (node (ref "U3") (pin "32") (pinfunction "IO3_32") (pintype "input"))
    )
    (net (code "53") (name "/NAND_D4") (class "Default")
      (node (ref "U1") (pin "G1") (pinfunction "RDATA4_G1") (pintype "input"))
      (node (ref "U3") (pin "41") (pinfunction "IO4_41") (pintype "input"))
    )
    (net (code "54") (name "/NAND_D5") (class "Default")
      (node (ref "U1") (pin "K7") (pinfunction "RDATA5_K7") (pintype "input"))
      (node (ref "U3") (pin "42") (pinfunction "IO5_42") (pintype "input"))
    )
    (net (code "55") (name "/NAND_D6") (class "Default")
      (node (ref "U1") (pin "G2") (pinfunction "RDATA6_G2") (pintype "input"))
      (node (ref "U3") (pin "43") (pinfunction "IO6_43") (pintype "input"))
    )
    (net (code "56") (name "/NAND_D7") (class "Default")
      (node (ref "U1") (pin "K8") (pinfunction "RDATA7_K8") (pintype "input"))
      (node (ref "U3") (pin "44") (pinfunction "IO7_44") (pintype "input"))
    )
    (net (code "57") (name "/NAND_RE") (class "Default")
      (node (ref "U1") (pin "D1") (pinfunction "nFRE/GPA20_D1") (pintype "input"))
      (node (ref "U3") (pin "8") (pinfunction "RE_8") (pintype "input"))
    )
    (net (code "58") (name "/NAND_RNB") (class "Default")
      (node (ref "U1") (pin "E3") (pinfunction "FRnB/GPM1_E3") (pintype "input"))
      (node (ref "U3") (pin "7") (pinfunction "R/B_7") (pintype "input"))
    )
    (net (code "59") (name "/NAND_WE") (class "Default")
      (node (ref "U1") (pin "H6") (pinfunction "nFWE/GPA19_H6") (pintype "input"))
      (node (ref "U3") (pin "18") (pinfunction "WE_18") (pintype "input"))
    )
    (net (code "60") (name "/TCK") (class "Default")
      (node (ref "CN1") (pin "5") (pinfunction "5_5") (pintype "input"))
      (node (ref "R13") (pin "1") (pinfunction "1_1") (pintype "input"))
      (node (ref "U1") (pin "P20") (pinfunction "TCK_P20") (pintype "input"))
    )
    (net (code "61") (name "/TDI") (class "Default")
      (node (ref "CN1") (pin "1") (pinfunction "1_1") (pintype "input"))
      (node (ref "R10") (pin "1") (pinfunction "1_1") (pintype "input"))
      (node (ref "U1") (pin "L17") (pinfunction "TDI_L17") (pintype "input"))
    )
    (net (code "62") (name "/TDO") (class "Default")
      (node (ref "CN1") (pin "4") (pinfunction "4_4") (pintype "input"))
      (node (ref "U1") (pin "M13") (pinfunction "TDO_M13") (pintype "output"))
    )
    (net (code "63") (name "/TMS") (class "Default")
      (node (ref "CN1") (pin "2") (pinfunction "2_2") (pintype "input"))
      (node (ref "R11") (pin "1") (pinfunction "1_1") (pintype "input"))
      (node (ref "U1") (pin "P19") (pinfunction "TMS_P19") (pintype "input"))
    )
    (net (code "64") (name "/TRST") (class "Default")
      (node (ref "CN1") (pin "3") (pinfunction "3_3") (pintype "input"))
      (node (ref "R12") (pin "1") (pinfunction "1_1") (pintype "input"))
      (node (ref "U1") (pin "L15") (pinfunction "nTRST_L15") (pintype "input"))
    )
    (net (code "65") (name "/UART_RX") (class "Default")
      (node (ref "H1") (pin "2") (pinfunction "2_2") (pintype "input"))
      (node (ref "U1") (pin "V6") (pinfunction "RXD0_V6") (pintype "input"))
    )
    (net (code "66") (name "/UART_TX") (class "Default")
      (node (ref "H1") (pin "3") (pinfunction "3_3") (pintype "input"))
      (node (ref "U1") (pin "P8") (pinfunction "TXD0_P8") (pintype "output"))
    )
    (net (code "67") (name "/UDEV_CLK") (class "Default")
      (node (ref "U1") (pin "K19") (pinfunction "XI_UDEV_K19") (pintype "output"))
      (node (ref "U1") (pin "V8") (pinfunction "CLKOUT0/GPH13_V8") (pintype "input"))
    )
    (net (code "68") (name "/USB_DN") (class "Default")
      (node (ref "U1") (pin "J20") (pinfunction "DM_UDEV_J20") (pintype "bidirectional"))
      (node (ref "USB2") (pin "5") (pinfunction "DN2_5") (pintype "input"))
      (node (ref "USB2") (pin "7") (pinfunction "DN1_7") (pintype "input"))
    )
    (net (code "69") (name "/USB_DP") (class "Default")
      (node (ref "U1") (pin "H19") (pinfunction "DP_UDEV_H19") (pintype "bidirectional"))
      (node (ref "USB2") (pin "6") (pinfunction "DP1_6") (pintype "input"))
      (node (ref "USB2") (pin "8") (pinfunction "DP2_8") (pintype "input"))
    )
    (net (code "70") (name "1V2") (class "Default")
      (node (ref "C12") (pin "1") (pinfunction "1_1") (pintype "input"))
      (node (ref "C35") (pin "1") (pinfunction "1_1") (pintype "input"))
      (node (ref "C36") (pin "1") (pinfunction "1_1") (pintype "input"))
      (node (ref "U1") (pin "J19") (pinfunction "VDDI_UDEV_J19") (pintype "input"))
      (node (ref "U1") (pin "R19") (pinfunction "VDDalive_R19") (pintype "input"))
      (node (ref "U9") (pin "2") (pinfunction "VOUT_2") (pintype "input"))
    )
    (net (code "71") (name "1V3") (class "Default")
      (node (ref "C13") (pin "1") (pinfunction "1_1") (pintype "input"))
      (node (ref "C14") (pin "1") (pinfunction "1_1") (pintype "input"))
      (node (ref "C15") (pin "1") (pinfunction "1_1") (pintype "input"))
      (node (ref "C17") (pin "1") (pinfunction "1_1") (pintype "input"))
      (node (ref "C18") (pin "1") (pinfunction "1_1") (pintype "input"))
      (node (ref "C19") (pin "1") (pinfunction "1_1") (pintype "input"))
      (node (ref "C20") (pin "1") (pinfunction "1_1") (pintype "input"))
      (node (ref "C27") (pin "1") (pinfunction "1_1") (pintype "input"))
      (node (ref "C28") (pin "1") (pinfunction "1_1") (pintype "input"))
      (node (ref "C8") (pin "1") (pinfunction "1_1") (pintype "input"))
      (node (ref "U1") (pin "G11") (pinfunction "VDDi_G11") (pintype "input"))
      (node (ref "U1") (pin "G13") (pinfunction "VDDi_G13") (pintype "input"))
      (node (ref "U1") (pin "J13") (pinfunction "VDDi_J13") (pintype "input"))
      (node (ref "U1") (pin "J2") (pinfunction "VDDiarm_J2") (pintype "input"))
      (node (ref "U1") (pin "J8") (pinfunction "VDDi_J8") (pintype "input"))
      (node (ref "U1") (pin "K2") (pinfunction "VDDiarm_K2") (pintype "input"))
      (node (ref "U1") (pin "L8") (pinfunction "VDDi_L8") (pintype "input"))
      (node (ref "U1") (pin "M7") (pinfunction "VDDi_M7") (pintype "input"))
      (node (ref "U1") (pin "N14") (pinfunction "VDDi_N14") (pintype "input"))
      (node (ref "U1") (pin "N3") (pinfunction "VDDiarm_N3") (pintype "input"))
      (node (ref "U1") (pin "P10") (pinfunction "VDDi_P10") (pintype "input"))
      (node (ref "U1") (pin "R3") (pinfunction "VDDiarm_R3") (pintype "input"))
      (node (ref "U1") (pin "V5") (pinfunction "VDDiarm_V5") (pintype "input"))
      (node (ref "U1") (pin "W8") (pinfunction "VDDiarm_W8") (pintype "input"))
      (node (ref "U1") (pin "W9") (pinfunction "VDDiarm_W9") (pintype "input"))
      (node (ref "U1") (pin "Y16") (pinfunction "VDD_MPLL_Y16") (pintype "input"))
      (node (ref "U1") (pin "Y17") (pinfunction "VDD_UPLL_Y17") (pintype "input"))
      (node (ref "U7") (pin "2") (pinfunction "VOUT_2") (pintype "input"))
    )
    (net (code "72") (name "1V8") (class "Default")
      (node (ref "C10") (pin "1") (pinfunction "1_1") (pintype "input"))
      (node (ref "C22") (pin "1") (pinfunction "1_1") (pintype "input"))
      (node (ref "C23") (pin "1") (pinfunction "1_1") (pintype "input"))
      (node (ref "C24") (pin "1") (pinfunction "1_1") (pintype "input"))
      (node (ref "C25") (pin "1") (pinfunction "1_1") (pintype "input"))
      (node (ref "C26") (pin "1") (pinfunction "1_1") (pintype "input"))
      (node (ref "C37") (pin "1") (pinfunction "1_1") (pintype "input"))
      (node (ref "C38") (pin "1") (pinfunction "1_1") (pintype "input"))
      (node (ref "C39") (pin "1") (pinfunction "1_1") (pintype "input"))
      (node (ref "C4") (pin "1") (pinfunction "1_1") (pintype "input"))
      (node (ref "C40") (pin "1") (pinfunction "1_1") (pintype "input"))
      (node (ref "C41") (pin "1") (pinfunction "1_1") (pintype "input"))
      (node (ref "C42") (pin "1") (pinfunction "1_1") (pintype "input"))
      (node (ref "R3") (pin "2") (pinfunction "2_2") (pintype "input"))
      (node (ref "U1") (pin "A12") (pinfunction "VDD_SDRAM_A12") (pintype "input"))
      (node (ref "U1") (pin "C16") (pinfunction "VDD_SDRAM_C16") (pintype "input"))
      (node (ref "U1") (pin "D19") (pinfunction "VDD_SDRAM_D19") (pintype "input"))
      (node (ref "U1") (pin "H14") (pinfunction "VDD_SDRAM_H14") (pintype "input"))
      (node (ref "U1") (pin "N12") (pinfunction "VDD_SDRAM_N12") (pintype "input"))
      (node (ref "U1") (pin "P13") (pinfunction "VDD_SDRAM_P13") (pintype "input"))
      (node (ref "U4") (pin "A1") (pinfunction "VDD_A1") (pintype "input"))
      (node (ref "U4") (pin "A9") (pinfunction "VDDQ_A9") (pintype "input"))
      (node (ref "U4") (pin "C1") (pinfunction "VDDQ_C1") (pintype "input"))
      (node (ref "U4") (pin "C3") (pinfunction "VDDQ_C3") (pintype "input"))
      (node (ref "U4") (pin "C7") (pinfunction "VDDQ_C7") (pintype "input"))
      (node (ref "U4") (pin "C9") (pinfunction "VDDQ_C9") (pintype "input"))
      (node (ref "U4") (pin "E1") (pinfunction "VDD_E1") (pintype "input"))
      (node (ref "U4") (pin "E9") (pinfunction "VDDQ_E9") (pintype "input"))
      (node (ref "U4") (pin "G1") (pinfunction "VDDQ_G1") (pintype "input"))
      (node (ref "U4") (pin "G3") (pinfunction "VDDQ_G3") (pintype "input"))
      (node (ref "U4") (pin "G7") (pinfunction "VDDQ_G7") (pintype "input"))
      (node (ref "U4") (pin "G9") (pinfunction "VDDQ_G9") (pintype "input"))
      (node (ref "U4") (pin "J1") (pinfunction "VDDL_J1") (pintype "input"))
      (node (ref "U4") (pin "J9") (pinfunction "VDD_J9") (pintype "input"))
      (node (ref "U4") (pin "M9") (pinfunction "VDD_M9") (pintype "input"))
      (node (ref "U4") (pin "R1") (pinfunction "VDD_R1") (pintype "input"))
      (node (ref "U8") (pin "2") (pinfunction "VOUT_2") (pintype "input"))
    )
    (net (code "73") (name "3V3") (class "Default")
      (node (ref "C30") (pin "1") (pinfunction "1_1") (pintype "input"))
      (node (ref "C31") (pin "1") (pinfunction "1_1") (pintype "input"))
      (node (ref "C32") (pin "1") (pinfunction "1_1") (pintype "input"))
      (node (ref "C33") (pin "1") (pinfunction "1_1") (pintype "input"))
      (node (ref "C34") (pin "1") (pinfunction "1_1") (pintype "input"))
      (node (ref "C43") (pin "1") (pinfunction "1_1") (pintype "input"))
      (node (ref "C6") (pin "1") (pinfunction "1_1") (pintype "input"))
      (node (ref "C7") (pin "1") (pinfunction "1_1") (pintype "input"))
      (node (ref "CN1") (pin "6") (pinfunction "6_6") (pintype "input"))
      (node (ref "R10") (pin "2") (pinfunction "2_2") (pintype "input"))
      (node (ref "R11") (pin "2") (pinfunction "2_2") (pintype "input"))
      (node (ref "R12") (pin "2") (pinfunction "2_2") (pintype "input"))
      (node (ref "R13") (pin "2") (pinfunction "2_2") (pintype "input"))
      (node (ref "R14") (pin "2") (pinfunction "2_2") (pintype "input"))
      (node (ref "R15") (pin "2") (pinfunction "2_2") (pintype "input"))
      (node (ref "U1") (pin "C5") (pinfunction "VDD_SRAM_C5") (pintype "input"))
      (node (ref "U1") (pin "F3") (pinfunction "VDD_SRAM_F3") (pintype "input"))
      (node (ref "U1") (pin "G18") (pinfunction "VDD33_G18") (pintype "input"))
      (node (ref "U1") (pin "G19") (pinfunction "VDD33_G19") (pintype "input"))
      (node (ref "U1") (pin "H1") (pinfunction "VDD_SRAM_H1") (pintype "input"))
      (node (ref "U1") (pin "L19") (pinfunction "VDD_USBOSC_L19") (pintype "input"))
      (node (ref "U1") (pin "M18") (pinfunction "VDD_OP3_M18") (pintype "input"))
      (node (ref "U1") (pin "N4") (pinfunction "GPC7_N4") (pintype "input"))
      (node (ref "U1") (pin "P18") (pinfunction "nBATT_FLT_P18") (pintype "input"))
      (node (ref "U1") (pin "R13") (pinfunction "AIN9_R13") (pintype "input"))
      (node (ref "U1") (pin "R14") (pinfunction "VDDA_ADC_R14") (pintype "input"))
      (node (ref "U1") (pin "T19") (pinfunction "VDD_OP1_T19") (pintype "input"))
      (node (ref "U1") (pin "U15") (pinfunction "Vref_U15") (pintype "input"))
      (node (ref "U1") (pin "U16") (pinfunction "OM3_U16") (pintype "input"))
      (node (ref "U1") (pin "V14") (pinfunction "AIN7_V14") (pintype "input"))
      (node (ref "U1") (pin "W12") (pinfunction "VDD_SD_W12") (pintype "input"))
      (node (ref "U1") (pin "W19") (pinfunction "VDD_RTC_W19") (pintype "input"))
      (node (ref "U1") (pin "W20") (pinfunction "XTIrtc_W20") (pintype "input"))
      (node (ref "U1") (pin "Y6") (pinfunction "VDD_OP2_Y6") (pintype "input"))
      (node (ref "U3") (pin "12") (pinfunction "VCC_12") (pintype "input"))
      (node (ref "U3") (pin "19") (pinfunction "WP_19") (pintype "input"))
      (node (ref "U3") (pin "37") (pinfunction "VCC_37") (pintype "input"))
      (node (ref "U6") (pin "2") (pinfunction "VOUT_2") (pintype "input"))
      (node (ref "U7") (pin "3") (pinfunction "VIN_3") (pintype "input"))
    )
    (net (code "74") (name "5V") (class "Default")
      (node (ref "C11") (pin "1") (pinfunction "1_1") (pintype "input"))
      (node (ref "C5") (pin "1") (pinfunction "1_1") (pintype "input"))
      (node (ref "C9") (pin "1") (pinfunction "1_1") (pintype "input"))
      (node (ref "U6") (pin "3") (pinfunction "VIN_3") (pintype "input"))
      (node (ref "U8") (pin "3") (pinfunction "VIN_3") (pintype "input"))
      (node (ref "U9") (pin "3") (pinfunction "VIN_3") (pintype "input"))
      (node (ref "USB2") (pin "11") (pinfunction "VBUS_11") (pintype "input"))
      (node (ref "USB2") (pin "2") (pinfunction "VBUS_2") (pintype "input"))
    )
    (net (code "75") (name "GND") (class "Default")
      (node (ref "C1") (pin "1") (pinfunction "1_1") (pintype "input"))
      (node (ref "C10") (pin "2") (pinfunction "2_2") (pintype "input"))
      (node (ref "C11") (pin "2") (pinfunction "2_2") (pintype "input"))
      (node (ref "C12") (pin "2") (pinfunction "2_2") (pintype "input"))
      (node (ref "C13") (pin "2") (pinfunction "2_2") (pintype "input"))
      (node (ref "C14") (pin "2") (pinfunction "2_2") (pintype "input"))
      (node (ref "C15") (pin "2") (pinfunction "2_2") (pintype "input"))
      (node (ref "C17") (pin "2") (pinfunction "2_2") (pintype "input"))
      (node (ref "C18") (pin "2") (pinfunction "2_2") (pintype "input"))
      (node (ref "C19") (pin "2") (pinfunction "2_2") (pintype "input"))
      (node (ref "C2") (pin "1") (pinfunction "1_1") (pintype "input"))
      (node (ref "C20") (pin "2") (pinfunction "2_2") (pintype "input"))
      (node (ref "C22") (pin "2") (pinfunction "2_2") (pintype "input"))
      (node (ref "C23") (pin "2") (pinfunction "2_2") (pintype "input"))
      (node (ref "C24") (pin "2") (pinfunction "2_2") (pintype "input"))
      (node (ref "C25") (pin "2") (pinfunction "2_2") (pintype "input"))
      (node (ref "C26") (pin "2") (pinfunction "2_2") (pintype "input"))
      (node (ref "C27") (pin "2") (pinfunction "2_2") (pintype "input"))
      (node (ref "C28") (pin "2") (pinfunction "2_2") (pintype "input"))
      (node (ref "C3") (pin "1") (pinfunction "1_1") (pintype "input"))
      (node (ref "C30") (pin "2") (pinfunction "2_2") (pintype "input"))
      (node (ref "C31") (pin "2") (pinfunction "2_2") (pintype "input"))
      (node (ref "C32") (pin "2") (pinfunction "2_2") (pintype "input"))
      (node (ref "C33") (pin "2") (pinfunction "2_2") (pintype "input"))
      (node (ref "C34") (pin "2") (pinfunction "2_2") (pintype "input"))
      (node (ref "C35") (pin "2") (pinfunction "2_2") (pintype "input"))
      (node (ref "C36") (pin "2") (pinfunction "2_2") (pintype "input"))
      (node (ref "C37") (pin "2") (pinfunction "2_2") (pintype "input"))
      (node (ref "C38") (pin "2") (pinfunction "2_2") (pintype "input"))
      (node (ref "C39") (pin "2") (pinfunction "2_2") (pintype "input"))
      (node (ref "C40") (pin "2") (pinfunction "2_2") (pintype "input"))
      (node (ref "C41") (pin "2") (pinfunction "2_2") (pintype "input"))
      (node (ref "C42") (pin "2") (pinfunction "2_2") (pintype "input"))
      (node (ref "C43") (pin "2") (pinfunction "2_2") (pintype "input"))
      (node (ref "C44") (pin "2") (pinfunction "2_2") (pintype "input"))
      (node (ref "C45") (pin "2") (pinfunction "2_2") (pintype "input"))
      (node (ref "C5") (pin "2") (pinfunction "2_2") (pintype "input"))
      (node (ref "C6") (pin "2") (pinfunction "2_2") (pintype "input"))
      (node (ref "C7") (pin "2") (pinfunction "2_2") (pintype "input"))
      (node (ref "C8") (pin "2") (pinfunction "2_2") (pintype "input"))
      (node (ref "C9") (pin "2") (pinfunction "2_2") (pintype "input"))
      (node (ref "CN1") (pin "7") (pinfunction "7_7") (pintype "input"))
      (node (ref "H1") (pin "1") (pinfunction "1_1") (pintype "input"))
      (node (ref "LED1") (pin "1") (pinfunction "K_1") (pintype "input"))
      (node (ref "LED2") (pin "1") (pinfunction "K_1") (pintype "input"))
      (node (ref "LED3") (pin "1") (pinfunction "K_1") (pintype "input"))
      (node (ref "R1") (pin "2") (pinfunction "2_2") (pintype "input"))
      (node (ref "R4") (pin "1") (pinfunction "1_1") (pintype "input"))
      (node (ref "R8") (pin "1") (pinfunction "1_1") (pintype "input"))
      (node (ref "R9") (pin "1") (pinfunction "1_1") (pintype "input"))
      (node (ref "U1") (pin "B11") (pinfunction "VSS_SDRAM_B11") (pintype "input"))
      (node (ref "U1") (pin "B5") (pinfunction "VSS_SRAM_B5") (pintype "input"))
      (node (ref "U1") (pin "C15") (pinfunction "VSS_SDRAM_C15") (pintype "input"))
      (node (ref "U1") (pin "D18") (pinfunction "VSS_SDRAM_D18") (pintype "input"))
      (node (ref "U1") (pin "E2") (pinfunction "VSS_SRAM_E2") (pintype "input"))
      (node (ref "U1") (pin "H11") (pinfunction "VSSi_H11") (pintype "input"))
      (node (ref "U1") (pin "H13") (pinfunction "VSSi_H13") (pintype "input"))
      (node (ref "U1") (pin "H18") (pinfunction "VSS33T_H18") (pintype "input"))
      (node (ref "U1") (pin "J17") (pinfunction "VSS33T_J17") (pintype "input"))
      (node (ref "U1") (pin "J3") (pinfunction "VSSi_J3") (pintype "input"))
      (node (ref "U1") (pin "J7") (pinfunction "VSSi_J7") (pintype "input"))
      (node (ref "U1") (pin "K20") (pinfunction "VSSIP_UDEV_K20") (pintype "input"))
      (node (ref "U1") (pin "K3") (pinfunction "VSSiarm_K3") (pintype "input"))
      (node (ref "U1") (pin "L1") (pinfunction "GPC6_L1") (pintype "input"))
      (node (ref "U1") (pin "L20") (pinfunction "VSS33C_L20") (pintype "input"))
      (node (ref "U1") (pin "L3") (pinfunction "VSSiarm_L3") (pintype "input"))
      (node (ref "U1") (pin "L6") (pinfunction "VSSi_L6") (pintype "input"))
      (node (ref "U1") (pin "M19") (pinfunction "VSS_OP3_M19") (pintype "input"))
      (node (ref "U1") (pin "M6") (pinfunction "GPC5_M6") (pintype "input"))
      (node (ref "U1") (pin "M8") (pinfunction "VSSi_M8") (pintype "input"))
      (node (ref "U1") (pin "N10") (pinfunction "VSSi_N10") (pintype "input"))
      (node (ref "U1") (pin "N11") (pinfunction "AIN3_N11") (pintype "input"))
      (node (ref "U1") (pin "N13") (pinfunction "VSSi_N13") (pintype "input"))
      (node (ref "U1") (pin "P11") (pinfunction "VSSA_ADC_P11") (pintype "input"))
      (node (ref "U1") (pin "P12") (pinfunction "AIN5_P12") (pintype "input"))
      (node (ref "U1") (pin "P15") (pinfunction "EXTCLK_P15") (pintype "input"))
      (node (ref "U1") (pin "P3") (pinfunction "VSSiarm_P3") (pintype "input"))
      (node (ref "U1") (pin "P4") (pinfunction "VSSiarm_P4") (pintype "input"))
      (node (ref "U1") (pin "R17") (pinfunction "OM0_R17") (pintype "input"))
      (node (ref "U1") (pin "R20") (pinfunction "VSSalive_R20") (pintype "input"))
      (node (ref "U1") (pin "T20") (pinfunction "VSS_OP1_T20") (pintype "input"))
      (node (ref "U1") (pin "U14") (pinfunction "AIN1_U14") (pintype "input"))
      (node (ref "U1") (pin "U17") (pinfunction "OM1_U17") (pintype "input"))
      (node (ref "U1") (pin "U7") (pinfunction "VSSiarm_U7") (pintype "input"))
      (node (ref "U1") (pin "U8") (pinfunction "VSSiarm_U8") (pintype "input"))
      (node (ref "U1") (pin "U9") (pinfunction "VSSiarm_U9") (pintype "input"))
      (node (ref "U1") (pin "V15") (pinfunction "VSS_MPLL_V15") (pintype "input"))
      (node (ref "U1") (pin "V17") (pinfunction "AIN6_V17") (pintype "input"))
      (node (ref "U1") (pin "V18") (pinfunction "OM4_V18") (pintype "input"))
      (node (ref "U1") (pin "V19") (pinfunction "OM2_V19") (pintype "input"))
      (node (ref "U1") (pin "W16") (pinfunction "VSS_UPLL_W16") (pintype "input"))
      (node (ref "U1") (pin "W17") (pinfunction "AIN8_W17") (pintype "input"))
      (node (ref "U1") (pin "W18") (pinfunction "AIN2_W18") (pintype "input"))
      (node (ref "U1") (pin "W7") (pinfunction "VSS_OP2_W7") (pintype "input"))
      (node (ref "U1") (pin "Y13") (pinfunction "VSS_SD_Y13") (pintype "input"))
      (node (ref "U1") (pin "Y18") (pinfunction "AIN4_Y18") (pintype "input"))
      (node (ref "U1") (pin "Y19") (pinfunction "AIN0_Y19") (pintype "input"))
      (node (ref "U3") (pin "13") (pinfunction "VSS_13") (pintype "input"))
      (node (ref "U3") (pin "36") (pinfunction "VSS_36") (pintype "input"))
      (node (ref "U4") (pin "A3") (pinfunction "VSS_A3") (pintype "input"))
      (node (ref "U4") (pin "A7") (pinfunction "VSSQ_A7") (pintype "input"))
      (node (ref "U4") (pin "B2") (pinfunction "VSSQ_B2") (pintype "input"))
      (node (ref "U4") (pin "B8") (pinfunction "VSSQ_B8") (pintype "input"))
      (node (ref "U4") (pin "D2") (pinfunction "VSSQ_D2") (pintype "input"))
      (node (ref "U4") (pin "D8") (pinfunction "VSSQ_D8") (pintype "input"))
      (node (ref "U4") (pin "E3") (pinfunction "VSS_E3") (pintype "input"))
      (node (ref "U4") (pin "E7") (pinfunction "VSSQ_E7") (pintype "input"))
      (node (ref "U4") (pin "F2") (pinfunction "VSSQ_F2") (pintype "input"))
      (node (ref "U4") (pin "F8") (pinfunction "VSSQ_F8") (pintype "input"))
      (node (ref "U4") (pin "H2") (pinfunction "VSSQ_H2") (pintype "input"))
      (node (ref "U4") (pin "H8") (pinfunction "VSSQ_H8") (pintype "input"))
      (node (ref "U4") (pin "J3") (pinfunction "VSS_J3") (pintype "input"))
      (node (ref "U4") (pin "J7") (pinfunction "VSSDL_J7") (pintype "input"))
      (node (ref "U4") (pin "K9") (pinfunction "ODT_K9") (pintype "input"))
      (node (ref "U4") (pin "L1") (pinfunction "NC_L1") (pintype "input"))
      (node (ref "U4") (pin "N1") (pinfunction "VSS_N1") (pintype "input"))
      (node (ref "U4") (pin "P9") (pinfunction "VSS_P9") (pintype "input"))
      (node (ref "U6") (pin "1") (pinfunction "VSS_1") (pintype "input"))
      (node (ref "U7") (pin "1") (pinfunction "VSS_1") (pintype "input"))
      (node (ref "U8") (pin "1") (pinfunction "VSS_1") (pintype "input"))
      (node (ref "U9") (pin "1") (pinfunction "VSS_1") (pintype "input"))
      (node (ref "USB2") (pin "1") (pinfunction "GND_1") (pintype "input"))
      (node (ref "USB2") (pin "12") (pinfunction "GND_12") (pintype "input"))
      (node (ref "USB2") (pin "13") (pinfunction "SHELL_13") (pintype "input"))
      (node (ref "USB2") (pin "14") (pinfunction "SHELL_14") (pintype "input"))
    )
    (net (code "76") (name "Net-(LED1-A)") (class "Default")
      (node (ref "LED1") (pin "2") (pinfunction "A_2") (pintype "input"))
      (node (ref "R5") (pin "2") (pinfunction "2_2") (pintype "input"))
    )
    (net (code "77") (name "Net-(LED2-A)") (class "Default")
      (node (ref "LED2") (pin "2") (pinfunction "A_2") (pintype "input"))
      (node (ref "R6") (pin "2") (pinfunction "2_2") (pintype "input"))
    )
    (net (code "78") (name "Net-(LED3-A)") (class "Default")
      (node (ref "LED3") (pin "2") (pinfunction "A_2") (pintype "input"))
      (node (ref "R7") (pin "2") (pinfunction "2_2") (pintype "input"))
    )
    (net (code "79") (name "Net-(U1-REXT)") (class "Default")
      (node (ref "R1") (pin "1") (pinfunction "1_1") (pintype "input"))
      (node (ref "U1") (pin "H20") (pinfunction "REXT_H20") (pintype "output"))
    )
    (net (code "80") (name "Net-(U1-UPLLCAP)") (class "Default")
      (node (ref "C45") (pin "1") (pinfunction "1_1") (pintype "input"))
      (node (ref "U1") (pin "V16") (pinfunction "UPLLCAP_V16") (pintype "input"))
    )
    (net (code "81") (name "Net-(U1-XTIpll)") (class "Default")
      (node (ref "C1") (pin "2") (pinfunction "2_2") (pintype "input"))
      (node (ref "U1") (pin "V20") (pinfunction "XTIpll_V20") (pintype "input"))
      (node (ref "X2") (pin "2") (pinfunction "OSC2_2") (pintype "input"))
    )
    (net (code "82") (name "Net-(U1-XTOpll)") (class "Default")
      (node (ref "C2") (pin "2") (pinfunction "2_2") (pintype "input"))
      (node (ref "U1") (pin "U18") (pinfunction "XTOpll_U18") (pintype "output"))
      (node (ref "X2") (pin "1") (pinfunction "OSC1_1") (pintype "input"))
    )
    (net (code "83") (name "Net-(U1-nRESET)") (class "Default")
      (node (ref "C44") (pin "1") (pinfunction "1_1") (pintype "input"))
      (node (ref "R14") (pin "1") (pinfunction "1_1") (pintype "input"))
      (node (ref "U1") (pin "M14") (pinfunction "nRESET_M14") (pintype "input"))
    )
    (net (code "84") (name "Net-(U1-nWAIT)") (class "Default")
      (node (ref "R15") (pin "1") (pinfunction "1_1") (pintype "input"))
      (node (ref "U1") (pin "D3") (pinfunction "nWAIT_D3") (pintype "input"))
    )
    (net (code "85") (name "Net-(U4-VREF)") (class "Default")
      (node (ref "C3") (pin "2") (pinfunction "2_2") (pintype "input"))
      (node (ref "C4") (pin "2") (pinfunction "2_2") (pintype "input"))
      (node (ref "R3") (pin "1") (pinfunction "1_1") (pintype "input"))
      (node (ref "R4") (pin "2") (pinfunction "2_2") (pintype "input"))
      (node (ref "U4") (pin "J2") (pinfunction "VREF_J2") (pintype "input"))
    )
    (net (code "86") (name "Net-(USB2-CC1)") (class "Default")
      (node (ref "R8") (pin "2") (pinfunction "2_2") (pintype "input"))
      (node (ref "USB2") (pin "4") (pinfunction "CC1_4") (pintype "input"))
    )
    (net (code "87") (name "Net-(USB2-CC2)") (class "Default")
      (node (ref "R9") (pin "2") (pinfunction "2_2") (pintype "input"))
      (node (ref "USB2") (pin "10") (pinfunction "CC2_10") (pintype "input"))
    )
    (net (code "88") (name "unconnected-(CN1-Pad8)") (class "Default")
      (node (ref "CN1") (pin "8") (pinfunction "8_8") (pintype "input"))
    )
    (net (code "89") (name "unconnected-(CN1-Pad9)") (class "Default")
      (node (ref "CN1") (pin "9") (pinfunction "9_9") (pintype "input"))
    )
    (net (code "90") (name "unconnected-(U1-CLKOUT1{slash}GPH14-PadY7)") (class "Default")
      (node (ref "U1") (pin "Y7") (pinfunction "CLKOUT1/GPH14_Y7") (pintype "input+no_connect"))
    )
    (net (code "91") (name "unconnected-(U1-DQM2{slash}GPA25-PadB16)") (class "Default")
      (node (ref "U1") (pin "B16") (pinfunction "DQM2/GPA25_B16") (pintype "input+no_connect"))
    )
    (net (code "92") (name "unconnected-(U1-DQM3{slash}GPA26-PadD14)") (class "Default")
      (node (ref "U1") (pin "D14") (pinfunction "DQM3/GPA26_D14") (pintype "input+no_connect"))
    )
    (net (code "93") (name "unconnected-(U1-PWR_EN-PadM15)") (class "Default")
      (node (ref "U1") (pin "M15") (pinfunction "PWR_EN_M15") (pintype "input+no_connect"))
    )
    (net (code "94") (name "unconnected-(U1-RADDR0{slash}GPA0-PadB3)") (class "Default")
      (node (ref "U1") (pin "B3") (pinfunction "RADDR0/GPA0_B3") (pintype "input+no_connect"))
    )
    (net (code "95") (name "unconnected-(U1-RADDR1-PadD7)") (class "Default")
      (node (ref "U1") (pin "D7") (pinfunction "RADDR1_D7") (pintype "input+no_connect"))
    )
    (net (code "96") (name "unconnected-(U1-RADDR2-PadA3)") (class "Default")
      (node (ref "U1") (pin "A3") (pinfunction "RADDR2_A3") (pintype "input+no_connect"))
    )
    (net (code "97") (name "unconnected-(U1-RADDR3-PadH8)") (class "Default")
      (node (ref "U1") (pin "H8") (pinfunction "RADDR3_H8") (pintype "input+no_connect"))
    )
    (net (code "98") (name "unconnected-(U1-RADDR4-PadC4)") (class "Default")
      (node (ref "U1") (pin "C4") (pinfunction "RADDR4_C4") (pintype "input+no_connect"))
    )
    (net (code "99") (name "unconnected-(U1-RADDR5-PadG8)") (class "Default")
      (node (ref "U1") (pin "G8") (pinfunction "RADDR5_G8") (pintype "input+no_connect"))
    )
    (net (code "100") (name "unconnected-(U1-RADDR6-PadB4)") (class "Default")
      (node (ref "U1") (pin "B4") (pinfunction "RADDR6_B4") (pintype "input+no_connect"))
    )
    (net (code "101") (name "unconnected-(U1-RADDR7-PadF8)") (class "Default")
      (node (ref "U1") (pin "F8") (pinfunction "RADDR7_F8") (pintype "input+no_connect"))
    )
    (net (code "102") (name "unconnected-(U1-RADDR8-PadA4)") (class "Default")
      (node (ref "U1") (pin "A4") (pinfunction "RADDR8_A4") (pintype "input+no_connect"))
    )
    (net (code "103") (name "unconnected-(U1-RADDR9-PadD8)") (class "Default")
      (node (ref "U1") (pin "D8") (pinfunction "RADDR9_D8") (pintype "input+no_connect"))
    )
    (net (code "104") (name "unconnected-(U1-RADDR10-PadA5)") (class "Default")
      (node (ref "U1") (pin "A5") (pinfunction "RADDR10_A5") (pintype "input+no_connect"))
    )
    (net (code "105") (name "unconnected-(U1-RADDR11-PadH9)") (class "Default")
      (node (ref "U1") (pin "H9") (pinfunction "RADDR11_H9") (pintype "input+no_connect"))
    )
    (net (code "106") (name "unconnected-(U1-RADDR12-PadC6)") (class "Default")
      (node (ref "U1") (pin "C6") (pinfunction "RADDR12_C6") (pintype "input+no_connect"))
    )
    (net (code "107") (name "unconnected-(U1-RADDR13-PadG9)") (class "Default")
      (node (ref "U1") (pin "G9") (pinfunction "RADDR13_G9") (pintype "input+no_connect"))
    )
    (net (code "108") (name "unconnected-(U1-RADDR14-PadB6)") (class "Default")
      (node (ref "U1") (pin "B6") (pinfunction "RADDR14_B6") (pintype "input+no_connect"))
    )
    (net (code "109") (name "unconnected-(U1-RADDR15-PadF9)") (class "Default")
      (node (ref "U1") (pin "F9") (pinfunction "RADDR15_F9") (pintype "input+no_connect"))
    )
    (net (code "110") (name "unconnected-(U1-RADDR16{slash}GPA1-PadA6)") (class "Default")
      (node (ref "U1") (pin "A6") (pinfunction "RADDR16/GPA1_A6") (pintype "input+no_connect"))
    )
    (net (code "111") (name "unconnected-(U1-RADDR17{slash}GPA2-PadD9)") (class "Default")
      (node (ref "U1") (pin "D9") (pinfunction "RADDR17/GPA2_D9") (pintype "input+no_connect"))
    )
    (net (code "112") (name "unconnected-(U1-RADDR18{slash}GPA3-PadC7)") (class "Default")
      (node (ref "U1") (pin "C7") (pinfunction "RADDR18/GPA3_C7") (pintype "input+no_connect"))
    )
    (net (code "113") (name "unconnected-(U1-RADDR19{slash}GPA4-PadC9)") (class "Default")
      (node (ref "U1") (pin "C9") (pinfunction "RADDR19/GPA4_C9") (pintype "input+no_connect"))
    )
    (net (code "114") (name "unconnected-(U1-RADDR20{slash}GPA5-PadB7)") (class "Default")
      (node (ref "U1") (pin "B7") (pinfunction "RADDR20/GPA5_B7") (pintype "input+no_connect"))
    )
    (net (code "115") (name "unconnected-(U1-RADDR21{slash}GPA6-PadH10)") (class "Default")
      (node (ref "U1") (pin "H10") (pinfunction "RADDR21/GPA6_H10") (pintype "input+no_connect"))
    )
    (net (code "116") (name "unconnected-(U1-RADDR22{slash}GPA7-PadA7)") (class "Default")
      (node (ref "U1") (pin "A7") (pinfunction "RADDR22/GPA7_A7") (pintype "input+no_connect"))
    )
    (net (code "117") (name "unconnected-(U1-RADDR23{slash}GPA8-PadG10)") (class "Default")
      (node (ref "U1") (pin "G10") (pinfunction "RADDR23/GPA8_G10") (pintype "input+no_connect"))
    )
    (net (code "118") (name "unconnected-(U1-RADDR24{slash}GPA9-PadC8)") (class "Default")
      (node (ref "U1") (pin "C8") (pinfunction "RADDR24/GPA9_C8") (pintype "input+no_connect"))
    )
    (net (code "119") (name "unconnected-(U1-RADDR25{slash}RDATA_OEN-PadF10)") (class "Default")
      (node (ref "U1") (pin "F10") (pinfunction "RADDR25/RDATA_OEN_F10") (pintype "input+no_connect"))
    )
    (net (code "120") (name "unconnected-(U1-RDATA8-PadG3)") (class "Default")
      (node (ref "U1") (pin "G3") (pinfunction "RDATA8_G3") (pintype "input+no_connect"))
    )
    (net (code "121") (name "unconnected-(U1-RDATA9-PadK4)") (class "Default")
      (node (ref "U1") (pin "K4") (pinfunction "RDATA9_K4") (pintype "input+no_connect"))
    )
    (net (code "122") (name "unconnected-(U1-RDATA10-PadF1)") (class "Default")
      (node (ref "U1") (pin "F1") (pinfunction "RDATA10_F1") (pintype "input+no_connect"))
    )
    (net (code "123") (name "unconnected-(U1-RDATA11-PadJ6)") (class "Default")
      (node (ref "U1") (pin "J6") (pinfunction "RDATA11_J6") (pintype "input+no_connect"))
    )
    (net (code "124") (name "unconnected-(U1-RDATA12-PadF2)") (class "Default")
      (node (ref "U1") (pin "F2") (pinfunction "RDATA12_F2") (pintype "input+no_connect"))
    )
    (net (code "125") (name "unconnected-(U1-RDATA13-PadJ4)") (class "Default")
      (node (ref "U1") (pin "J4") (pinfunction "RDATA13_J4") (pintype "input+no_connect"))
    )
    (net (code "126") (name "unconnected-(U1-RDATA14-PadE1)") (class "Default")
      (node (ref "U1") (pin "E1") (pinfunction "RDATA14_E1") (pintype "input+no_connect"))
    )
    (net (code "127") (name "unconnected-(U1-RDATA15-PadH7)") (class "Default")
      (node (ref "U1") (pin "H7") (pinfunction "RDATA15_H7") (pintype "input+no_connect"))
    )
    (net (code "128") (name "unconnected-(U1-RSMBWAIT{slash}GPM0-PadC2)") (class "Default")
      (node (ref "U1") (pin "C2") (pinfunction "RSMBWAIT/GPM0_C2") (pintype "input+no_connect"))
    )
    (net (code "129") (name "unconnected-(U1-RSMCLK{slash}GPA23-PadB1)") (class "Default")
      (node (ref "U1") (pin "B1") (pinfunction "RSMCLK/GPA23_B1") (pintype "input+no_connect"))
    )
    (net (code "130") (name "unconnected-(U1-RSMVAD{slash}GPA24-PadE4)") (class "Default")
      (node (ref "U1") (pin "E4") (pinfunction "RSMVAD/GPA24_E4") (pintype "input+no_connect"))
    )
    (net (code "131") (name "unconnected-(U1-SADDR13-PadA9)") (class "Default")
      (node (ref "U1") (pin "A9") (pinfunction "SADDR13_A9") (pintype "input+no_connect"))
    )
    (net (code "132") (name "unconnected-(U1-SDATA16{slash}GPK0-PadD20)") (class "Default")
      (node (ref "U1") (pin "D20") (pinfunction "SDATA16/GPK0_D20") (pintype "input+no_connect"))
    )
    (net (code "133") (name "unconnected-(U1-SDATA17{slash}GPK1-PadF17)") (class "Default")
      (node (ref "U1") (pin "F17") (pinfunction "SDATA17/GPK1_F17") (pintype "input+no_connect"))
    )
    (net (code "134") (name "unconnected-(U1-SDATA18{slash}GPK2-PadE18)") (class "Default")
      (node (ref "U1") (pin "E18") (pinfunction "SDATA18/GPK2_E18") (pintype "input+no_connect"))
    )
    (net (code "135") (name "unconnected-(U1-SDATA19{slash}GPK3-PadG15)") (class "Default")
      (node (ref "U1") (pin "G15") (pinfunction "SDATA19/GPK3_G15") (pintype "input+no_connect"))
    )
    (net (code "136") (name "unconnected-(U1-SDATA20{slash}GPK4-PadE19)") (class "Default")
      (node (ref "U1") (pin "E19") (pinfunction "SDATA20/GPK4_E19") (pintype "input+no_connect"))
    )
    (net (code "137") (name "unconnected-(U1-SDATA21{slash}GPK5-PadG17)") (class "Default")
      (node (ref "U1") (pin "G17") (pinfunction "SDATA21/GPK5_G17") (pintype "input+no_connect"))
    )
    (net (code "138") (name "unconnected-(U1-SDATA22{slash}GPK6-PadE20)") (class "Default")
      (node (ref "U1") (pin "E20") (pinfunction "SDATA22/GPK6_E20") (pintype "input+no_connect"))
    )
    (net (code "139") (name "unconnected-(U1-SDATA23{slash}GPK7-PadH15)") (class "Default")
      (node (ref "U1") (pin "H15") (pinfunction "SDATA23/GPK7_H15") (pintype "input+no_connect"))
    )
    (net (code "140") (name "unconnected-(U1-SDATA24{slash}GPK8-PadF18)") (class "Default")
      (node (ref "U1") (pin "F18") (pinfunction "SDATA24/GPK8_F18") (pintype "input+no_connect"))
    )
    (net (code "141") (name "unconnected-(U1-SDATA25{slash}GPK9-PadH17)") (class "Default")
      (node (ref "U1") (pin "H17") (pinfunction "SDATA25/GPK9_H17") (pintype "input+no_connect"))
    )
    (net (code "142") (name "unconnected-(U1-SDATA26{slash}GPK10-PadF19)") (class "Default")
      (node (ref "U1") (pin "F19") (pinfunction "SDATA26/GPK10_F19") (pintype "input+no_connect"))
    )
    (net (code "143") (name "unconnected-(U1-SDATA27{slash}GPK11-PadJ14)") (class "Default")
      (node (ref "U1") (pin "J14") (pinfunction "SDATA27/GPK11_J14") (pintype "input+no_connect"))
    )
    (net (code "144") (name "unconnected-(U1-SDATA28{slash}GPK12-PadF20)") (class "Default")
      (node (ref "U1") (pin "F20") (pinfunction "SDATA28/GPK12_F20") (pintype "input+no_connect"))
    )
    (net (code "145") (name "unconnected-(U1-SDATA29{slash}GPK13-PadJ15)") (class "Default")
      (node (ref "U1") (pin "J15") (pinfunction "SDATA29/GPK13_J15") (pintype "input+no_connect"))
    )
    (net (code "146") (name "unconnected-(U1-SDATA30{slash}GPK14-PadG20)") (class "Default")
      (node (ref "U1") (pin "G20") (pinfunction "SDATA30/GPK14_G20") (pintype "input+no_connect"))
    )
    (net (code "147") (name "unconnected-(U1-SDATA31{slash}GPK15-PadJ18)") (class "Default")
      (node (ref "U1") (pin "J18") (pinfunction "SDATA31/GPK15_J18") (pintype "input+no_connect"))
    )
    (net (code "148") (name "unconnected-(U1-TOUT3{slash}GPB3-PadW1)") (class "Default")
      (node (ref "U1") (pin "W1") (pinfunction "TOUT3/GPB3_W1") (pintype "input+no_connect"))
    )
    (net (code "149") (name "unconnected-(U1-XO_UDEV-PadK18)") (class "Default")
      (node (ref "U1") (pin "K18") (pinfunction "XO_UDEV_K18") (pintype "output+no_connect"))
    )
    (net (code "150") (name "unconnected-(U1-XTOrtc-PadT17)") (class "Default")
      (node (ref "U1") (pin "T17") (pinfunction "XTOrtc_T17") (pintype "output+no_connect"))
    )
    (net (code "151") (name "unconnected-(U1-nRBE0-PadC3)") (class "Default")
      (node (ref "U1") (pin "C3") (pinfunction "nRBE0_C3") (pintype "input+no_connect"))
    )
    (net (code "152") (name "unconnected-(U1-nRBE1-PadF7)") (class "Default")
      (node (ref "U1") (pin "F7") (pinfunction "nRBE1_F7") (pintype "input+no_connect"))
    )
    (net (code "153") (name "unconnected-(U1-nRCS0-PadD5)") (class "Default")
      (node (ref "U1") (pin "D5") (pinfunction "nRCS0_D5") (pintype "input+no_connect"))
    )
    (net (code "154") (name "unconnected-(U1-nRCS1{slash}GPA12-PadB2)") (class "Default")
      (node (ref "U1") (pin "B2") (pinfunction "nRCS1/GPA12_B2") (pintype "input+no_connect"))
    )
    (net (code "155") (name "unconnected-(U1-nRCS2{slash}GPA13-PadD4)") (class "Default")
      (node (ref "U1") (pin "D4") (pinfunction "nRCS2/GPA13_D4") (pintype "input+no_connect"))
    )
    (net (code "156") (name "unconnected-(U1-nRCS3{slash}GPA14-PadF4)") (class "Default")
      (node (ref "U1") (pin "F4") (pinfunction "nRCS3/GPA14_F4") (pintype "input+no_connect"))
    )
    (net (code "157") (name "unconnected-(U1-nRCS4{slash}GPA15-PadC1)") (class "Default")
      (node (ref "U1") (pin "C1") (pinfunction "nRCS4/GPA15_C1") (pintype "input+no_connect"))
    )
    (net (code "158") (name "unconnected-(U1-nRCS5{slash}GPA16-PadG6)") (class "Default")
      (node (ref "U1") (pin "G6") (pinfunction "nRCS5/GPA16_G6") (pintype "input+no_connect"))
    )
    (net (code "159") (name "unconnected-(U1-nROE-PadD6)") (class "Default")
      (node (ref "U1") (pin "D6") (pinfunction "nROE_D6") (pintype "input+no_connect"))
    )
    (net (code "160") (name "unconnected-(U1-nRSTOUT{slash}GPA21-PadN18)") (class "Default")
      (node (ref "U1") (pin "N18") (pinfunction "nRSTOUT/GPA21_N18") (pintype "input+no_connect"))
    )
    (net (code "161") (name "unconnected-(U1-nRWE-PadA2)") (class "Default")
      (node (ref "U1") (pin "A2") (pinfunction "nRWE_A2") (pintype "input+no_connect"))
    )
    (net (code "162") (name "unconnected-(U1-nSCS1-PadB15)") (class "Default")
      (node (ref "U1") (pin "B15") (pinfunction "nSCS1_B15") (pintype "input+no_connect"))
    )
    (net (code "163") (name "unconnected-(U1-nXBACK{slash}GPB5-PadU6)") (class "Default")
      (node (ref "U1") (pin "U6") (pinfunction "nXBACK/GPB5_U6") (pintype "input+no_connect"))
    )
    (net (code "164") (name "unconnected-(U1-nXBREQ{slash}RTCK{slash}GPB6-PadV4)") (class "Default")
      (node (ref "U1") (pin "V4") (pinfunction "nXBREQ/RTCK/GPB6_V4") (pintype "input+no_connect"))
    )
    (net (code "165") (name "unconnected-(U1-nXDACK0{slash}I2S0_SDO1{slash}GPB9-PadW4)") (class "Default")
      (node (ref "U1") (pin "W4") (pinfunction "nXDACK0/I2S0_SDO1/GPB9_W4") (pintype "input+no_connect"))
    )
    (net (code "166") (name "unconnected-(U1-nXDREQ0{slash}I2S0_SDO2{slash}GPB10-PadU5)") (class "Default")
      (node (ref "U1") (pin "U5") (pinfunction "nXDREQ0/I2S0_SDO2/GPB10_U5") (pintype "input+no_connect"))
    )
    (net (code "167") (name "unconnected-(U3-NC-Pad1)") (class "Default")
      (node (ref "U3") (pin "1") (pinfunction "NC_1") (pintype "input+no_connect"))
    )
    (net (code "168") (name "unconnected-(U3-NC-Pad2)") (class "Default")
      (node (ref "U3") (pin "2") (pinfunction "NC_2") (pintype "input+no_connect"))
    )
    (net (code "169") (name "unconnected-(U3-NC-Pad3)") (class "Default")
      (node (ref "U3") (pin "3") (pinfunction "NC_3") (pintype "input+no_connect"))
    )
    (net (code "170") (name "unconnected-(U3-NC-Pad4)") (class "Default")
      (node (ref "U3") (pin "4") (pinfunction "NC_4") (pintype "input+no_connect"))
    )
    (net (code "171") (name "unconnected-(U3-NC-Pad5)") (class "Default")
      (node (ref "U3") (pin "5") (pinfunction "NC_5") (pintype "input+no_connect"))
    )
    (net (code "172") (name "unconnected-(U3-NC-Pad6)") (class "Default")
      (node (ref "U3") (pin "6") (pinfunction "NC_6") (pintype "input+no_connect"))
    )
    (net (code "173") (name "unconnected-(U3-NC-Pad10)") (class "Default")
      (node (ref "U3") (pin "10") (pinfunction "NC_10") (pintype "input+no_connect"))
    )
    (net (code "174") (name "unconnected-(U3-NC-Pad11)") (class "Default")
      (node (ref "U3") (pin "11") (pinfunction "NC_11") (pintype "input+no_connect"))
    )
    (net (code "175") (name "unconnected-(U3-NC-Pad14)") (class "Default")
      (node (ref "U3") (pin "14") (pinfunction "NC_14") (pintype "input+no_connect"))
    )
    (net (code "176") (name "unconnected-(U3-NC-Pad15)") (class "Default")
      (node (ref "U3") (pin "15") (pinfunction "NC_15") (pintype "input+no_connect"))
    )
    (net (code "177") (name "unconnected-(U3-NC-Pad20)") (class "Default")
      (node (ref "U3") (pin "20") (pinfunction "NC_20") (pintype "input+no_connect"))
    )
    (net (code "178") (name "unconnected-(U3-NC-Pad21)") (class "Default")
      (node (ref "U3") (pin "21") (pinfunction "NC_21") (pintype "input+no_connect"))
    )
    (net (code "179") (name "unconnected-(U3-NC-Pad22)") (class "Default")
      (node (ref "U3") (pin "22") (pinfunction "NC_22") (pintype "input+no_connect"))
    )
    (net (code "180") (name "unconnected-(U3-NC-Pad23)") (class "Default")
      (node (ref "U3") (pin "23") (pinfunction "NC_23") (pintype "input+no_connect"))
    )
    (net (code "181") (name "unconnected-(U3-NC-Pad24)") (class "Default")
      (node (ref "U3") (pin "24") (pinfunction "NC_24") (pintype "input+no_connect"))
    )
    (net (code "182") (name "unconnected-(U3-NC-Pad25)") (class "Default")
      (node (ref "U3") (pin "25") (pinfunction "NC_25") (pintype "input+no_connect"))
    )
    (net (code "183") (name "unconnected-(U3-NC-Pad26)") (class "Default")
      (node (ref "U3") (pin "26") (pinfunction "NC_26") (pintype "input+no_connect"))
    )
    (net (code "184") (name "unconnected-(U3-NC-Pad27)") (class "Default")
      (node (ref "U3") (pin "27") (pinfunction "NC_27") (pintype "input+no_connect"))
    )
    (net (code "185") (name "unconnected-(U3-NC-Pad28)") (class "Default")
      (node (ref "U3") (pin "28") (pinfunction "NC_28") (pintype "input+no_connect"))
    )
    (net (code "186") (name "unconnected-(U3-NC-Pad33)") (class "Default")
      (node (ref "U3") (pin "33") (pinfunction "NC_33") (pintype "input+no_connect"))
    )
    (net (code "187") (name "unconnected-(U3-NC-Pad34)") (class "Default")
      (node (ref "U3") (pin "34") (pinfunction "NC_34") (pintype "input+no_connect"))
    )
    (net (code "188") (name "unconnected-(U3-NC-Pad35)") (class "Default")
      (node (ref "U3") (pin "35") (pinfunction "NC_35") (pintype "input+no_connect"))
    )
    (net (code "189") (name "unconnected-(U3-NC-Pad38)") (class "Default")
      (node (ref "U3") (pin "38") (pinfunction "NC_38") (pintype "input+no_connect"))
    )
    (net (code "190") (name "unconnected-(U3-NC-Pad39)") (class "Default")
      (node (ref "U3") (pin "39") (pinfunction "NC_39") (pintype "input+no_connect"))
    )
    (net (code "191") (name "unconnected-(U3-NC-Pad40)") (class "Default")
      (node (ref "U3") (pin "40") (pinfunction "NC_40") (pintype "input+no_connect"))
    )
    (net (code "192") (name "unconnected-(U3-NC-Pad45)") (class "Default")
      (node (ref "U3") (pin "45") (pinfunction "NC_45") (pintype "input+no_connect"))
    )
    (net (code "193") (name "unconnected-(U3-NC-Pad46)") (class "Default")
      (node (ref "U3") (pin "46") (pinfunction "NC_46") (pintype "input+no_connect"))
    )
    (net (code "194") (name "unconnected-(U3-NC-Pad47)") (class "Default")
      (node (ref "U3") (pin "47") (pinfunction "NC_47") (pintype "input+no_connect"))
    )
    (net (code "195") (name "unconnected-(U3-NC-Pad48)") (class "Default")
      (node (ref "U3") (pin "48") (pinfunction "NC_48") (pintype "input+no_connect"))
    )
    (net (code "196") (name "unconnected-(U4-LDQS#-PadE8)") (class "Default")
      (node (ref "U4") (pin "E8") (pinfunction "LDQS#_E8") (pintype "input+no_connect"))
    )
    (net (code "197") (name "unconnected-(U4-NC-PadA2)") (class "Default")
      (node (ref "U4") (pin "A2") (pinfunction "NC_A2") (pintype "input+no_connect"))
    )
    (net (code "198") (name "unconnected-(U4-NC-PadE2)") (class "Default")
      (node (ref "U4") (pin "E2") (pinfunction "NC_E2") (pintype "input+no_connect"))
    )
    (net (code "199") (name "unconnected-(U4-NC-PadR3)") (class "Default")
      (node (ref "U4") (pin "R3") (pinfunction "NC_R3") (pintype "input+no_connect"))
    )
    (net (code "200") (name "unconnected-(U4-NC-PadR7)") (class "Default")
      (node (ref "U4") (pin "R7") (pinfunction "NC_R7") (pintype "input+no_connect"))
    )
    (net (code "201") (name "unconnected-(U4-NC-PadR8)") (class "Default")
      (node (ref "U4") (pin "R8") (pinfunction "NC_R8") (pintype "input+no_connect"))
    )
    (net (code "202") (name "unconnected-(U4-UDQS#-PadA8)") (class "Default")
      (node (ref "U4") (pin "A8") (pinfunction "UDQS#_A8") (pintype "input+no_connect"))
    )
    (net (code "203") (name "unconnected-(USB2-SBU1-Pad9)") (class "Default")
      (node (ref "USB2") (pin "9") (pinfunction "SBU1_9") (pintype "input"))
    )
    (net (code "204") (name "unconnected-(USB2-SBU2-Pad3)") (class "Default")
      (node (ref "USB2") (pin "3") (pinfunction "SBU2_3") (pintype "input"))
    )
  )
)
